# reclone-rise.net
KiCad netlist of a schematic drawn in EAGLE
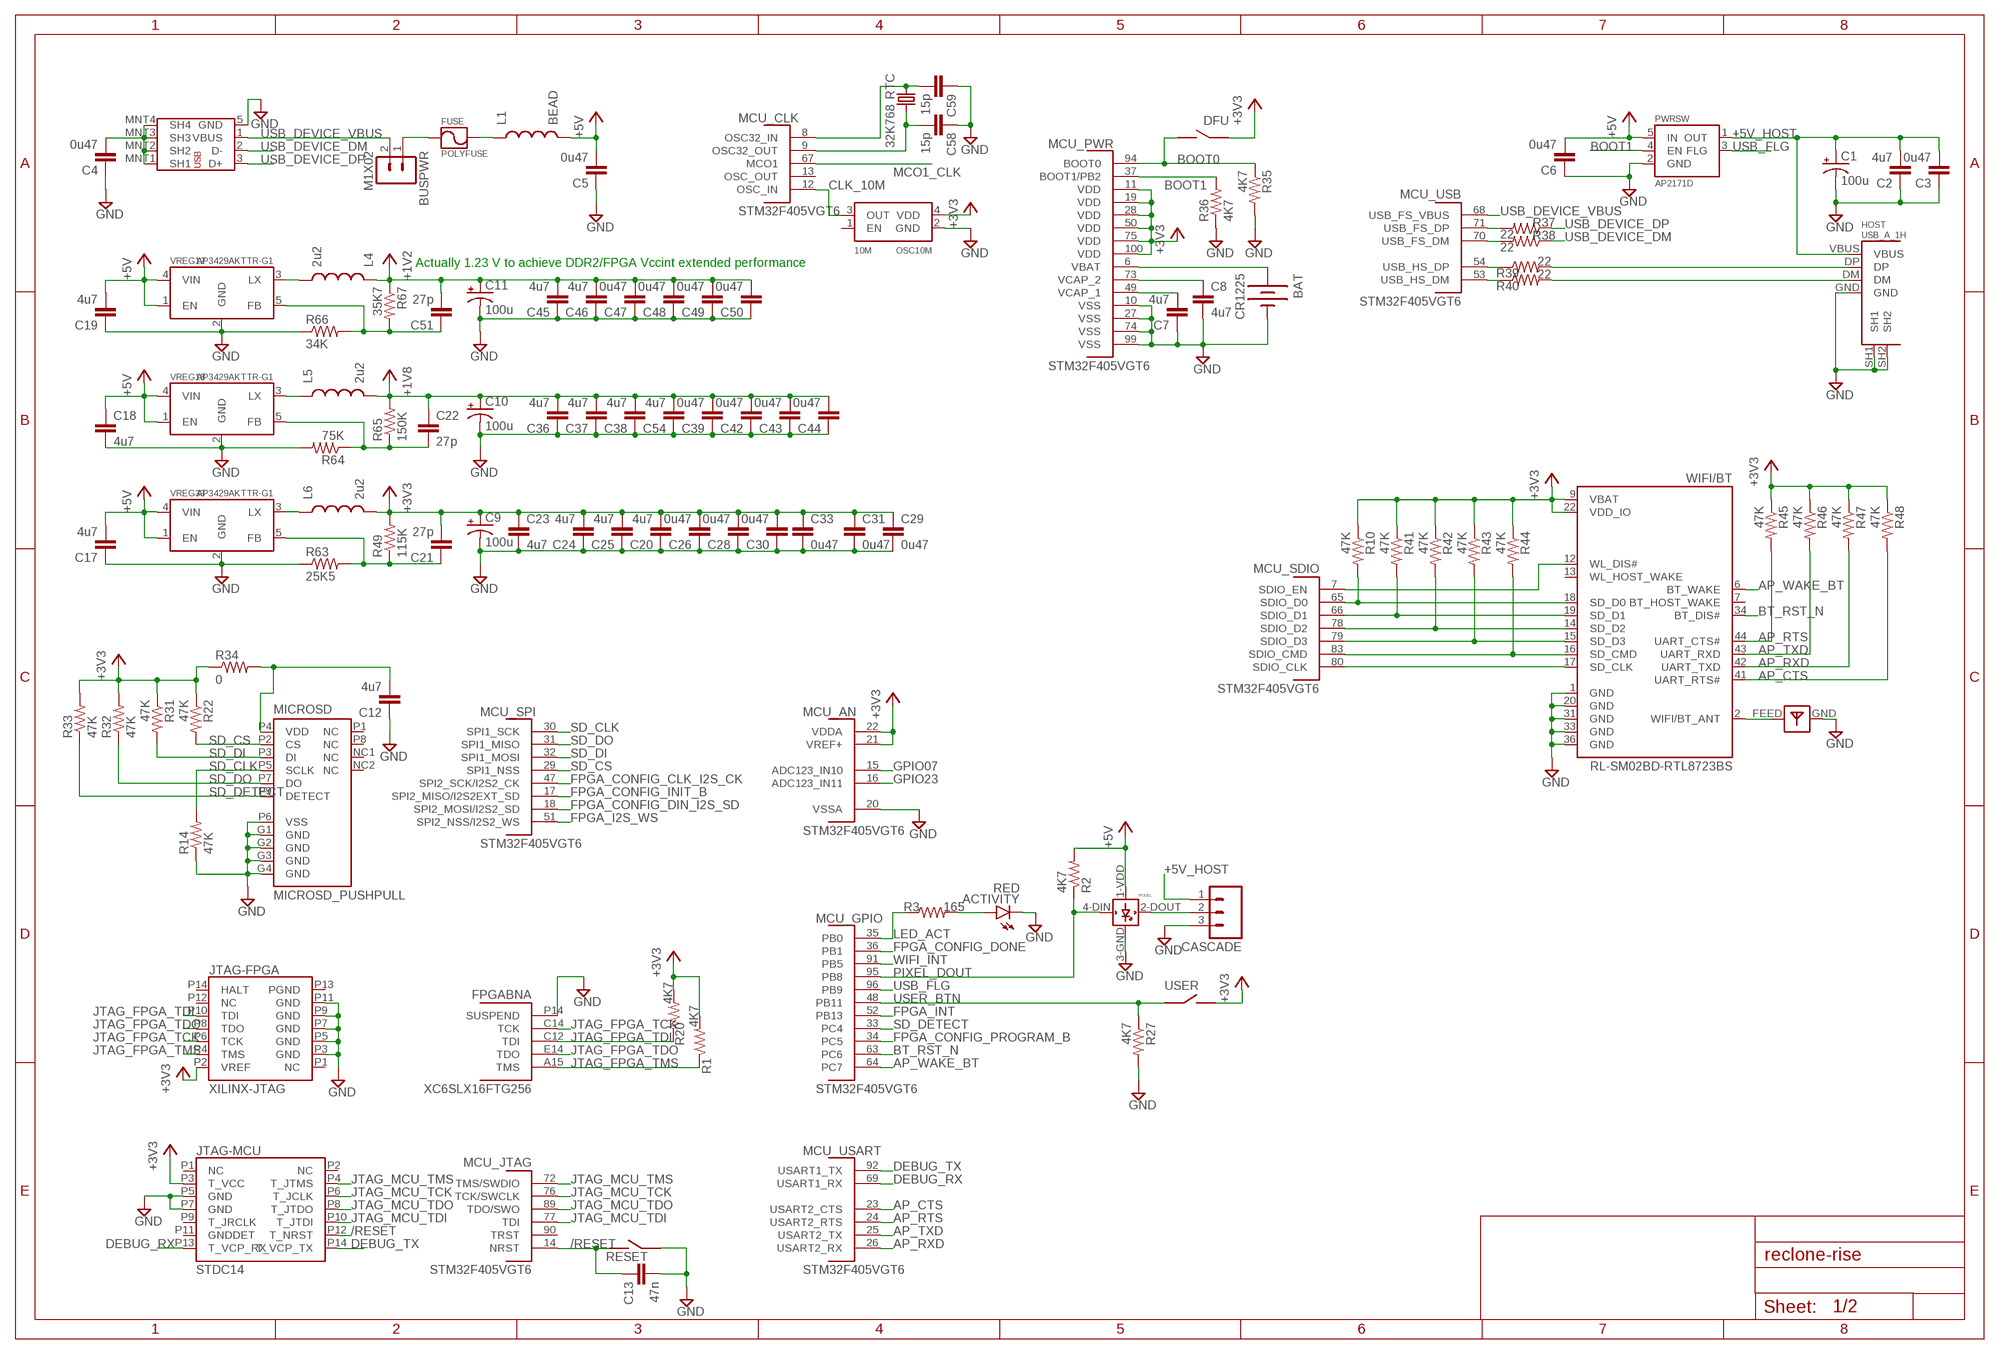
[diagram p0: schematic, sheet 1]
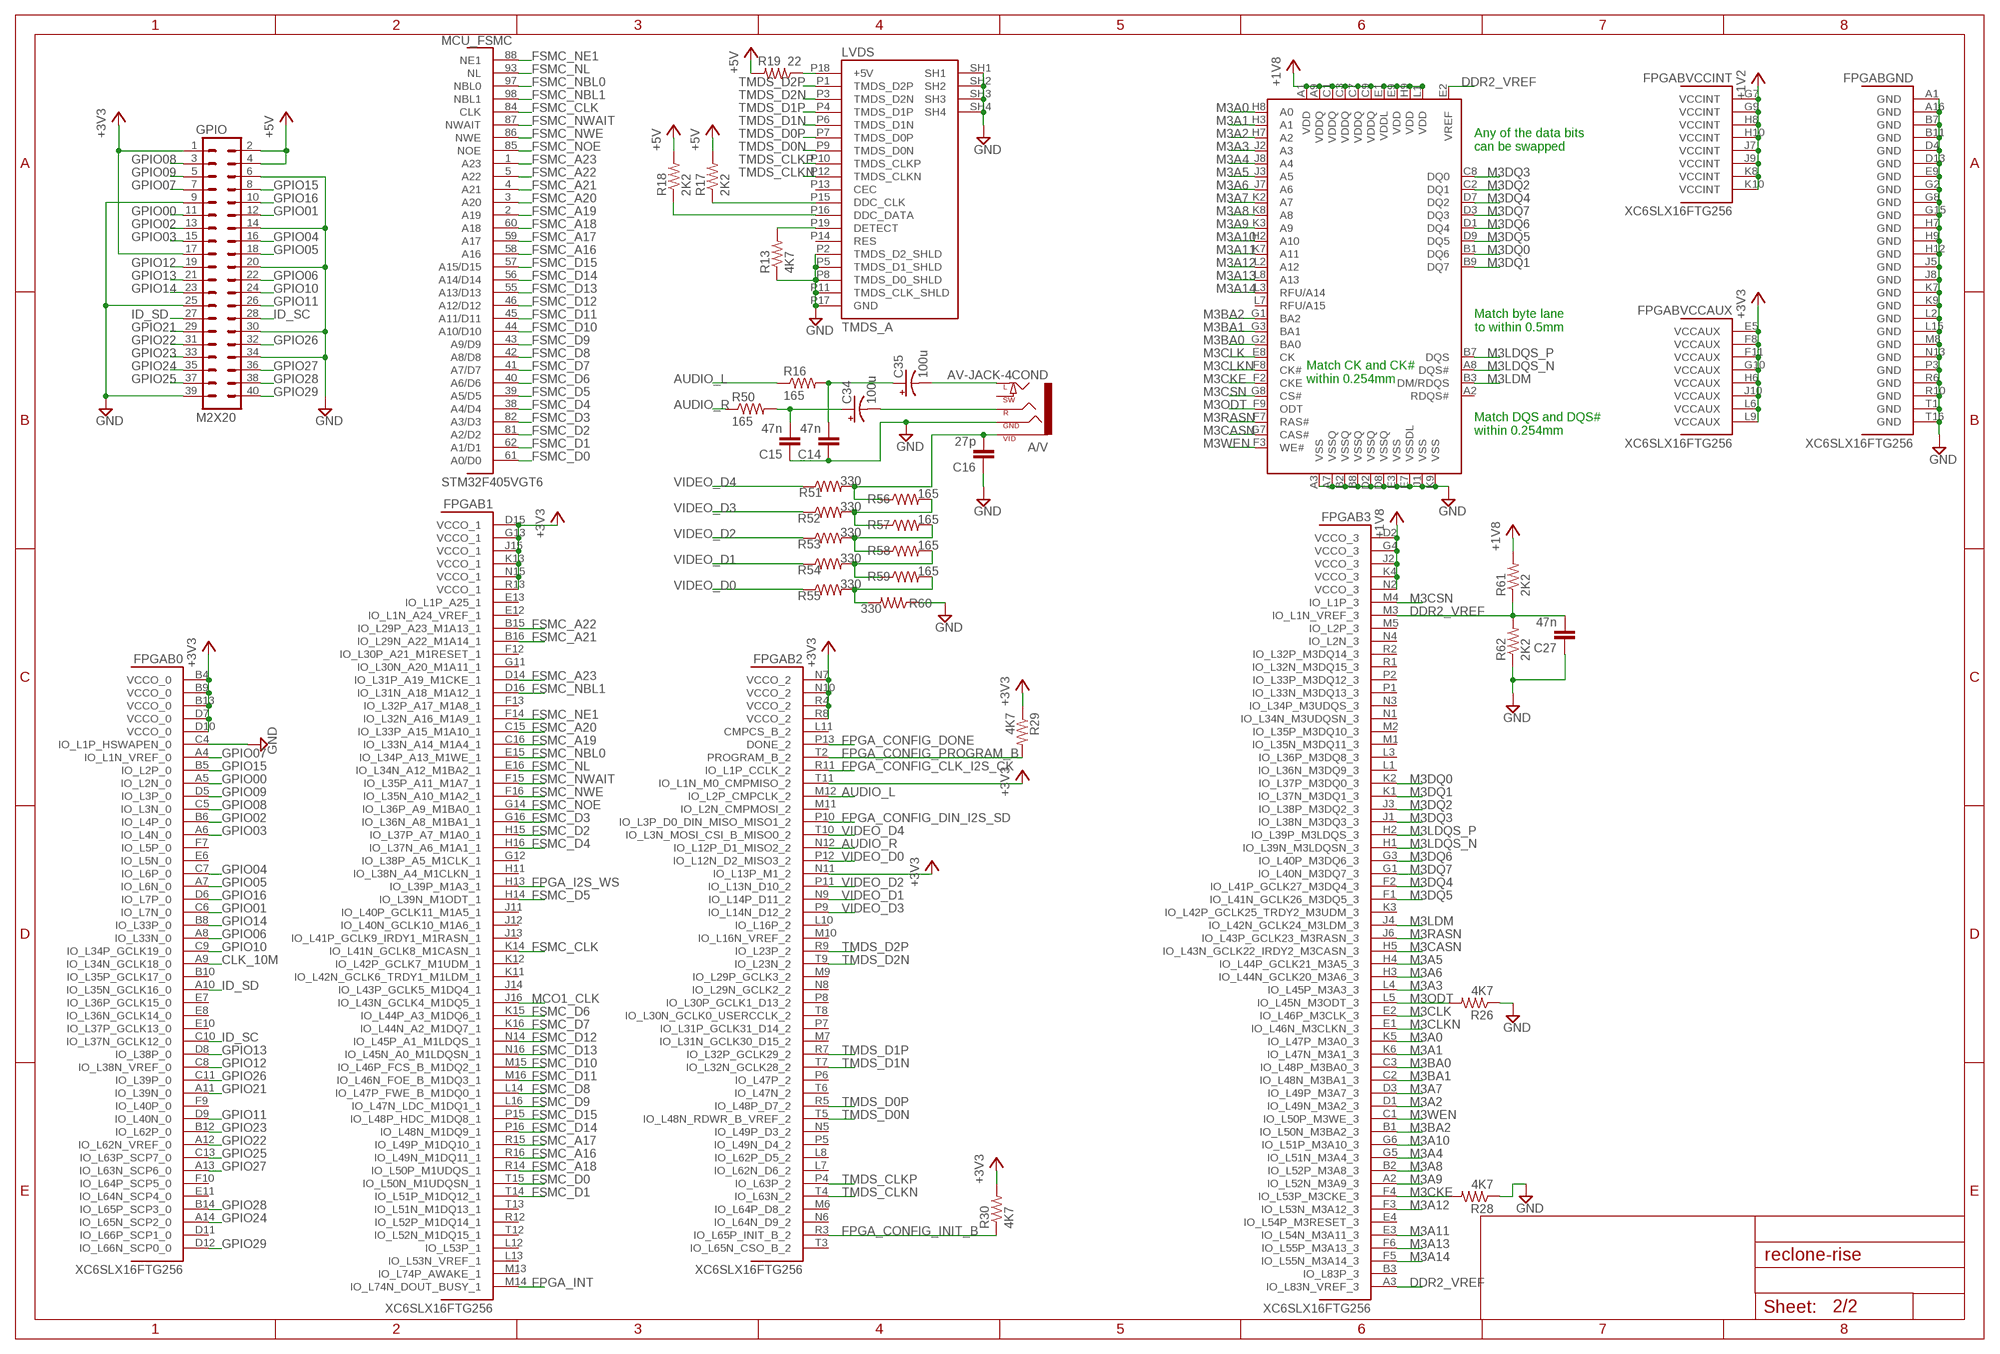
[diagram p1: schematic, sheet 2]

(export (version "E")
  (design (tool "Eeschema 10.0.6"))
  (components
    (comp (ref "A/V")
      (value "AV-JACK-4COND")
      (footprint "eagle-import:AV-JACK-3.5MM-4COND-SMD")
      (fields (field (name "MANF") "CUI Devices"))
      (libsource (lib "eagle-import") (part "AV-JACK-4COND"))
    )
    (comp (ref "C14")
      (value "47n")
      (footprint "eagle-import:0603-CAP")
      (fields (field (name "MANF") "Samsung Electro-Mechanics"))
      (libsource (lib "eagle-import") (part "CAP0603-CAP"))
    )
    (comp (ref "C15")
      (value "47n")
      (footprint "eagle-import:0603-CAP")
      (fields (field (name "MANF") "Samsung Electro-Mechanics"))
      (libsource (lib "eagle-import") (part "CAP0603-CAP"))
    )
    (comp (ref "C16")
      (value "27p")
      (footprint "eagle-import:0603-CAP")
      (fields (field (name "MANF") "KEMET"))
      (libsource (lib "eagle-import") (part "CAP0603-CAP"))
    )
    (comp (ref "C27")
      (value "47n")
      (footprint "eagle-import:0603-CAP")
      (fields (field (name "MANF") "Samsung Electro-Mechanics"))
      (libsource (lib "eagle-import") (part "CAP0603-CAP"))
    )
    (comp (ref "C34")
      (value "100u")
      (footprint "eagle-import:EIA3216")
      (fields (field (name "MANF") "Samsung Electro-Mechanics"))
      (libsource (lib "eagle-import") (part "CAP_POL1206"))
    )
    (comp (ref "C35")
      (value "100u")
      (footprint "eagle-import:EIA3216")
      (fields (field (name "MANF") "Samsung Electro-Mechanics"))
      (libsource (lib "eagle-import") (part "CAP_POL1206"))
    )
    (comp (ref "FPGA")
      (value "XC6SLX16FTG256")
      (footprint "eagle-import:FT256")
      (fields
        (field (name "DIGIKEY#") "122-1672-ND")
        (field (name "MANF") "Xilinx Inc.")
        (field (name "MANF#") "XC6SLX16-2FTG256C")
      )
      (libsource (lib "eagle-import") (part "XC6SLX16FTG256"))
    )
    (comp (ref "GPIO")
      (value "M2X20")
      (footprint "eagle-import:2X20")
      (fields (field (name "MANF") "Sullins Connector Solutions"))
      (libsource (lib "eagle-import") (part "M2X20"))
    )
    (comp (ref "LVDS")
      (value "TMDS_A")
      (footprint "eagle-import:TMDS_A_SMT")
      (fields (field (name "MANF") "FCI"))
      (libsource (lib "eagle-import") (part "TMDS_A"))
    )
    (comp (ref "MCU")
      (value "STM32F405VGT6")
      (footprint "eagle-import:LQFP-100")
      (fields (field (name "MANF") "STMicroelectronics"))
      (libsource (lib "eagle-import") (part "STM32F405VGT6"))
    )
    (comp (ref "R13")
      (value "4K7")
      (footprint "eagle-import:0603-RES")
      (fields (field (name "MANF") "Yageo"))
      (libsource (lib "eagle-import") (part "RESISTOR0603-RES"))
    )
    (comp (ref "R16")
      (value "165")
      (footprint "eagle-import:0603-RES")
      (fields (field (name "MANF") "Yageo"))
      (libsource (lib "eagle-import") (part "RESISTOR0603-RES"))
    )
    (comp (ref "R17")
      (value "2K2")
      (footprint "eagle-import:0603-RES")
      (fields (field (name "MANF") "Yageo"))
      (libsource (lib "eagle-import") (part "RESISTOR0603-RES"))
    )
    (comp (ref "R18")
      (value "2K2")
      (footprint "eagle-import:0603-RES")
      (fields (field (name "MANF") "Yageo"))
      (libsource (lib "eagle-import") (part "RESISTOR0603-RES"))
    )
    (comp (ref "R19")
      (value "22")
      (footprint "eagle-import:0603-RES")
      (fields (field (name "MANF") "Yageo"))
      (libsource (lib "eagle-import") (part "RESISTOR0603-RES"))
    )
    (comp (ref "R26")
      (value "4K7")
      (footprint "eagle-import:0603-RES")
      (fields (field (name "MANF") "Yageo"))
      (libsource (lib "eagle-import") (part "RESISTOR0603-RES"))
    )
    (comp (ref "R28")
      (value "4K7")
      (footprint "eagle-import:0603-RES")
      (fields (field (name "MANF") "Yageo"))
      (libsource (lib "eagle-import") (part "RESISTOR0603-RES"))
    )
    (comp (ref "R29")
      (value "4K7")
      (footprint "eagle-import:0603-RES")
      (fields (field (name "MANF") "Yageo"))
      (libsource (lib "eagle-import") (part "RESISTOR0603-RES"))
    )
    (comp (ref "R30")
      (value "4K7")
      (footprint "eagle-import:0603-RES")
      (fields (field (name "MANF") "Yageo"))
      (libsource (lib "eagle-import") (part "RESISTOR0603-RES"))
    )
    (comp (ref "R50")
      (value "165")
      (footprint "eagle-import:0603-RES")
      (fields (field (name "MANF") "Yageo"))
      (libsource (lib "eagle-import") (part "RESISTOR0603-RES"))
    )
    (comp (ref "R51")
      (value "330")
      (footprint "eagle-import:0603-RES")
      (fields (field (name "MANF") "Yageo"))
      (libsource (lib "eagle-import") (part "RESISTOR0603-RES"))
    )
    (comp (ref "R52")
      (value "330")
      (footprint "eagle-import:0603-RES")
      (fields (field (name "MANF") "Yageo"))
      (libsource (lib "eagle-import") (part "RESISTOR0603-RES"))
    )
    (comp (ref "R53")
      (value "330")
      (footprint "eagle-import:0603-RES")
      (fields (field (name "MANF") "Yageo"))
      (libsource (lib "eagle-import") (part "RESISTOR0603-RES"))
    )
    (comp (ref "R54")
      (value "330")
      (footprint "eagle-import:0603-RES")
      (fields (field (name "MANF") "Yageo"))
      (libsource (lib "eagle-import") (part "RESISTOR0603-RES"))
    )
    (comp (ref "R55")
      (value "330")
      (footprint "eagle-import:0603-RES")
      (fields (field (name "MANF") "Yageo"))
      (libsource (lib "eagle-import") (part "RESISTOR0603-RES"))
    )
    (comp (ref "R56")
      (value "165")
      (footprint "eagle-import:0603-RES")
      (fields (field (name "MANF") "Yageo"))
      (libsource (lib "eagle-import") (part "RESISTOR0603-RES"))
    )
    (comp (ref "R57")
      (value "165")
      (footprint "eagle-import:0603-RES")
      (fields (field (name "MANF") "Yageo"))
      (libsource (lib "eagle-import") (part "RESISTOR0603-RES"))
    )
    (comp (ref "R58")
      (value "165")
      (footprint "eagle-import:0603-RES")
      (fields (field (name "MANF") "Yageo"))
      (libsource (lib "eagle-import") (part "RESISTOR0603-RES"))
    )
    (comp (ref "R59")
      (value "165")
      (footprint "eagle-import:0603-RES")
      (fields (field (name "MANF") "Yageo"))
      (libsource (lib "eagle-import") (part "RESISTOR0603-RES"))
    )
    (comp (ref "R60")
      (value "330")
      (footprint "eagle-import:0603-RES")
      (fields (field (name "MANF") "Yageo"))
      (libsource (lib "eagle-import") (part "RESISTOR0603-RES"))
    )
    (comp (ref "R61")
      (value "2K2")
      (footprint "eagle-import:0603-RES")
      (fields (field (name "MANF") "Yageo"))
      (libsource (lib "eagle-import") (part "RESISTOR0603-RES"))
    )
    (comp (ref "R62")
      (value "2K2")
      (footprint "eagle-import:0603-RES")
      (fields (field (name "MANF") "Yageo"))
      (libsource (lib "eagle-import") (part "RESISTOR0603-RES"))
    )
    (comp (ref "RAM")
      (value "DDR2_X8")
      (footprint "eagle-import:60-FBGA-9X11.5")
      (fields (field (name "MANF") "ISSI Integrated Silicon Solution Inc"))
      (libsource (lib "eagle-import") (part "DDR2_X8"))
    )
    (comp (ref "ACTIVITY")
      (value "RED")
      (footprint "eagle-import:LED-0603")
      (fields (field (name "MANF") "Wurth Electronics Inc."))
      (libsource (lib "eagle-import") (part "LED0603"))
    )
    (comp (ref "ANTENNA")
      (value "ANTENNA_MEANDER_2.4GHZ")
      (footprint "eagle-import:MEANDER_ANTENNA_2.4GHZ")
      (libsource (lib "eagle-import") (part "ANTENNA_MEANDER_2.4GHZ"))
    )
    (comp (ref "BAT")
      (value "CR1225")
      (footprint "eagle-import:BATTCON_12MM")
      (fields (field (name "MANF") "Keystone Electronics"))
      (libsource (lib "eagle-import") (part "BATTERY12MM"))
    )
    (comp (ref "BUSPWR")
      (value "M1X02")
      (footprint "eagle-import:1X2-RTANG")
      (fields (field (name "MANF") "Sullins Connector Solutions"))
      (libsource (lib "eagle-import") (part "M1X02"))
    )
    (comp (ref "C1")
      (value "100u")
      (footprint "eagle-import:EIA3216")
      (fields (field (name "MANF") "Samsung Electro-Mechanics"))
      (libsource (lib "eagle-import") (part "CAP_POL1206"))
    )
    (comp (ref "C2")
      (value "4u7")
      (footprint "eagle-import:0603-CAP")
      (fields (field (name "MANF") "Samsung Electro-Mechanics"))
      (libsource (lib "eagle-import") (part "CAP0603-CAP"))
    )
    (comp (ref "C3")
      (value "0u47")
      (footprint "eagle-import:0603-CAP")
      (fields (field (name "MANF") "Samsung Electro-Mechanics"))
      (libsource (lib "eagle-import") (part "CAP0603-CAP"))
    )
    (comp (ref "C4")
      (value "0u47")
      (footprint "eagle-import:0603-CAP")
      (fields (field (name "MANF") "Samsung Electro-Mechanics"))
      (libsource (lib "eagle-import") (part "CAP0603-CAP"))
    )
    (comp (ref "C5")
      (value "0u47")
      (footprint "eagle-import:0603-CAP")
      (fields (field (name "MANF") "Samsung Electro-Mechanics"))
      (libsource (lib "eagle-import") (part "CAP0603-CAP"))
    )
    (comp (ref "C6")
      (value "0u47")
      (footprint "eagle-import:0603-CAP")
      (fields (field (name "MANF") "Samsung Electro-Mechanics"))
      (libsource (lib "eagle-import") (part "CAP0603-CAP"))
    )
    (comp (ref "C7")
      (value "4u7")
      (footprint "eagle-import:0603-CAP")
      (fields (field (name "MANF") "Samsung Electro-Mechanics"))
      (libsource (lib "eagle-import") (part "CAP0603-CAP"))
    )
    (comp (ref "C8")
      (value "4u7")
      (footprint "eagle-import:0603-CAP")
      (fields (field (name "MANF") "Samsung Electro-Mechanics"))
      (libsource (lib "eagle-import") (part "CAP0603-CAP"))
    )
    (comp (ref "C9")
      (value "100u")
      (footprint "eagle-import:EIA3216")
      (fields (field (name "MANF") "Samsung Electro-Mechanics"))
      (libsource (lib "eagle-import") (part "CAP_POL1206"))
    )
    (comp (ref "C10")
      (value "100u")
      (footprint "eagle-import:EIA3216")
      (fields (field (name "MANF") "Samsung Electro-Mechanics"))
      (libsource (lib "eagle-import") (part "CAP_POL1206"))
    )
    (comp (ref "C11")
      (value "100u")
      (footprint "eagle-import:EIA3216")
      (fields (field (name "MANF") "Samsung Electro-Mechanics"))
      (libsource (lib "eagle-import") (part "CAP_POL1206"))
    )
    (comp (ref "C12")
      (value "4u7")
      (footprint "eagle-import:0603-CAP")
      (fields (field (name "MANF") "Samsung Electro-Mechanics"))
      (libsource (lib "eagle-import") (part "CAP0603-CAP"))
    )
    (comp (ref "C13")
      (value "47n")
      (footprint "eagle-import:0603-CAP")
      (fields (field (name "MANF") "Samsung Electro-Mechanics"))
      (libsource (lib "eagle-import") (part "CAP0603-CAP"))
    )
    (comp (ref "C17")
      (value "4u7")
      (footprint "eagle-import:0603-CAP")
      (fields (field (name "MANF") "Samsung Electro-Mechanics"))
      (libsource (lib "eagle-import") (part "CAP0603-CAP"))
    )
    (comp (ref "C18")
      (value "4u7")
      (footprint "eagle-import:0603-CAP")
      (fields (field (name "MANF") "Samsung Electro-Mechanics"))
      (libsource (lib "eagle-import") (part "CAP0603-CAP"))
    )
    (comp (ref "C19")
      (value "4u7")
      (footprint "eagle-import:0603-CAP")
      (fields (field (name "MANF") "Samsung Electro-Mechanics"))
      (libsource (lib "eagle-import") (part "CAP0603-CAP"))
    )
    (comp (ref "C20")
      (value "4u7")
      (footprint "eagle-import:0603-CAP")
      (fields (field (name "MANF") "Samsung Electro-Mechanics"))
      (libsource (lib "eagle-import") (part "CAP0603-CAP"))
    )
    (comp (ref "C21")
      (value "27p")
      (footprint "eagle-import:0603-CAP")
      (fields (field (name "MANF") "KEMET"))
      (libsource (lib "eagle-import") (part "CAP0603-CAP"))
    )
    (comp (ref "C22")
      (value "27p")
      (footprint "eagle-import:0603-CAP")
      (fields (field (name "MANF") "KEMET"))
      (libsource (lib "eagle-import") (part "CAP0603-CAP"))
    )
    (comp (ref "C23")
      (value "4u7")
      (footprint "eagle-import:0603-CAP")
      (fields (field (name "MANF") "Samsung Electro-Mechanics"))
      (libsource (lib "eagle-import") (part "CAP0603-CAP"))
    )
    (comp (ref "C24")
      (value "4u7")
      (footprint "eagle-import:0603-CAP")
      (fields (field (name "MANF") "Samsung Electro-Mechanics"))
      (libsource (lib "eagle-import") (part "CAP0603-CAP"))
    )
    (comp (ref "C25")
      (value "4u7")
      (footprint "eagle-import:0603-CAP")
      (fields (field (name "MANF") "Samsung Electro-Mechanics"))
      (libsource (lib "eagle-import") (part "CAP0603-CAP"))
    )
    (comp (ref "C26")
      (value "0u47")
      (footprint "eagle-import:0603-CAP")
      (fields (field (name "MANF") "Samsung Electro-Mechanics"))
      (libsource (lib "eagle-import") (part "CAP0603-CAP"))
    )
    (comp (ref "C28")
      (value "0u47")
      (footprint "eagle-import:0603-CAP")
      (fields (field (name "MANF") "Samsung Electro-Mechanics"))
      (libsource (lib "eagle-import") (part "CAP0603-CAP"))
    )
    (comp (ref "C29")
      (value "0u47")
      (footprint "eagle-import:0603-CAP")
      (fields (field (name "MANF") "Samsung Electro-Mechanics"))
      (libsource (lib "eagle-import") (part "CAP0603-CAP"))
    )
    (comp (ref "C30")
      (value "0u47")
      (footprint "eagle-import:0603-CAP")
      (fields (field (name "MANF") "Samsung Electro-Mechanics"))
      (libsource (lib "eagle-import") (part "CAP0603-CAP"))
    )
    (comp (ref "C31")
      (value "0u47")
      (footprint "eagle-import:0603-CAP")
      (fields (field (name "MANF") "Samsung Electro-Mechanics"))
      (libsource (lib "eagle-import") (part "CAP0603-CAP"))
    )
    (comp (ref "C33")
      (value "0u47")
      (footprint "eagle-import:0603-CAP")
      (fields (field (name "MANF") "Samsung Electro-Mechanics"))
      (libsource (lib "eagle-import") (part "CAP0603-CAP"))
    )
    (comp (ref "C36")
      (value "4u7")
      (footprint "eagle-import:0603-CAP")
      (fields (field (name "MANF") "Samsung Electro-Mechanics"))
      (libsource (lib "eagle-import") (part "CAP0603-CAP"))
    )
    (comp (ref "C37")
      (value "4u7")
      (footprint "eagle-import:0603-CAP")
      (fields (field (name "MANF") "Samsung Electro-Mechanics"))
      (libsource (lib "eagle-import") (part "CAP0603-CAP"))
    )
    (comp (ref "C38")
      (value "4u7")
      (footprint "eagle-import:0603-CAP")
      (fields (field (name "MANF") "Samsung Electro-Mechanics"))
      (libsource (lib "eagle-import") (part "CAP0603-CAP"))
    )
    (comp (ref "C39")
      (value "0u47")
      (footprint "eagle-import:0603-CAP")
      (fields (field (name "MANF") "Samsung Electro-Mechanics"))
      (libsource (lib "eagle-import") (part "CAP0603-CAP"))
    )
    (comp (ref "C42")
      (value "0u47")
      (footprint "eagle-import:0603-CAP")
      (fields (field (name "MANF") "Samsung Electro-Mechanics"))
      (libsource (lib "eagle-import") (part "CAP0603-CAP"))
    )
    (comp (ref "C43")
      (value "0u47")
      (footprint "eagle-import:0603-CAP")
      (fields (field (name "MANF") "Samsung Electro-Mechanics"))
      (libsource (lib "eagle-import") (part "CAP0603-CAP"))
    )
    (comp (ref "C44")
      (value "0u47")
      (footprint "eagle-import:0603-CAP")
      (fields (field (name "MANF") "Samsung Electro-Mechanics"))
      (libsource (lib "eagle-import") (part "CAP0603-CAP"))
    )
    (comp (ref "C45")
      (value "4u7")
      (footprint "eagle-import:0603-CAP")
      (fields (field (name "MANF") "Samsung Electro-Mechanics"))
      (libsource (lib "eagle-import") (part "CAP0603-CAP"))
    )
    (comp (ref "C46")
      (value "4u7")
      (footprint "eagle-import:0603-CAP")
      (fields (field (name "MANF") "Samsung Electro-Mechanics"))
      (libsource (lib "eagle-import") (part "CAP0603-CAP"))
    )
    (comp (ref "C47")
      (value "0u47")
      (footprint "eagle-import:0603-CAP")
      (fields (field (name "MANF") "Samsung Electro-Mechanics"))
      (libsource (lib "eagle-import") (part "CAP0603-CAP"))
    )
    (comp (ref "C48")
      (value "0u47")
      (footprint "eagle-import:0603-CAP")
      (fields (field (name "MANF") "Samsung Electro-Mechanics"))
      (libsource (lib "eagle-import") (part "CAP0603-CAP"))
    )
    (comp (ref "C49")
      (value "0u47")
      (footprint "eagle-import:0603-CAP")
      (fields (field (name "MANF") "Samsung Electro-Mechanics"))
      (libsource (lib "eagle-import") (part "CAP0603-CAP"))
    )
    (comp (ref "C50")
      (value "0u47")
      (footprint "eagle-import:0603-CAP")
      (fields (field (name "MANF") "Samsung Electro-Mechanics"))
      (libsource (lib "eagle-import") (part "CAP0603-CAP"))
    )
    (comp (ref "C51")
      (value "27p")
      (footprint "eagle-import:0603-CAP")
      (fields (field (name "MANF") "KEMET"))
      (libsource (lib "eagle-import") (part "CAP0603-CAP"))
    )
    (comp (ref "C54")
      (value "4u7")
      (footprint "eagle-import:0603-CAP")
      (fields (field (name "MANF") "Samsung Electro-Mechanics"))
      (libsource (lib "eagle-import") (part "CAP0603-CAP"))
    )
    (comp (ref "C58")
      (value "15p")
      (footprint "eagle-import:0603-CAP")
      (fields (field (name "MANF") "AVX Corporation"))
      (libsource (lib "eagle-import") (part "CAP0603-CAP"))
    )
    (comp (ref "C59")
      (value "15p")
      (footprint "eagle-import:0603-CAP")
      (fields (field (name "MANF") "AVX Corporation"))
      (libsource (lib "eagle-import") (part "CAP0603-CAP"))
    )
    (comp (ref "CASCADE")
      (value "M03PTH")
      (footprint "eagle-import:1X03")
      (libsource (lib "eagle-import") (part "M03PTH"))
    )
    (comp (ref "DEVICE")
      (value "USB-MICRO-B-SMD")
      (footprint "eagle-import:USB-MICRO-B-SMD")
      (fields (field (name "MANF") "FCI"))
      (libsource (lib "eagle-import") (part "USB-MICRO-B-SMD"))
    )
    (comp (ref "DFU")
      (value "PTS636")
      (footprint "eagle-import:PB_TACT_PTH_6X3.5")
      (fields (field (name "MANF") "C&K"))
      (libsource (lib "eagle-import") (part "PTS636"))
    )
    (comp (ref "FUSE")
      (value "POLYFUSE")
      (footprint "eagle-import:1206L")
      (fields (field (name "MANF") "Bourns Inc."))
      (libsource (lib "eagle-import") (part "POLYFUSE"))
    )
    (comp (ref "HOST")
      (value "USB_A_1H")
      (footprint "eagle-import:USB-A-1H")
      (fields (field (name "MANF") "Amphenol ICC (FCI)"))
      (libsource (lib "eagle-import") (part "USB_A_1H"))
    )
    (comp (ref "JTAG-FPGA")
      (value "XILINX-JTAG")
      (footprint "eagle-import:XILINX-JTAG")
      (fields (field (name "MANF") "Molex"))
      (libsource (lib "eagle-import") (part "XILINX-JTAG"))
    )
    (comp (ref "JTAG-MCU")
      (value "STDC14")
      (footprint "eagle-import:PTH_14_1.27")
      (fields (field (name "MANF") "CNC Tech"))
      (libsource (lib "eagle-import") (part "STDC14"))
    )
    (comp (ref "L1")
      (value "BEAD")
      (footprint "eagle-import:0603")
      (fields (field (name "MANF") "Murata Electronics"))
      (libsource (lib "eagle-import") (part "INDUCTOR0603"))
    )
    (comp (ref "L4")
      (value "2u2")
      (footprint "eagle-import:0805")
      (fields (field (name "MANF") "Samsung Electro-Mechanics"))
      (libsource (lib "eagle-import") (part "INDUCTOR0805"))
    )
    (comp (ref "L5")
      (value "2u2")
      (footprint "eagle-import:0805")
      (fields (field (name "MANF") "Samsung Electro-Mechanics"))
      (libsource (lib "eagle-import") (part "INDUCTOR0805"))
    )
    (comp (ref "L6")
      (value "2u2")
      (footprint "eagle-import:0805")
      (fields (field (name "MANF") "Samsung Electro-Mechanics"))
      (libsource (lib "eagle-import") (part "INDUCTOR0805"))
    )
    (comp (ref "MICROSD")
      (value "MICROSD_PUSHPULL")
      (footprint "eagle-import:MICROSD_PUSHPULL")
      (fields (field (name "MANF") "Molex"))
      (libsource (lib "eagle-import") (part "MICROSD_PUSHPULL"))
    )
    (comp (ref "OSC10M")
      (value "10M")
      (footprint "eagle-import:OSC-5X3.2")
      (fields (field (name "MANF") "Fox Electronics"))
      (libsource (lib "eagle-import") (part "OSC_ENABLED_SMD"))
    )
    (comp (ref "PIXEL")
      (value "WS2812B")
      (footprint "eagle-import:WS2812B")
      (fields (field (name "MANF") "SparkFun Electronics"))
      (libsource (lib "eagle-import") (part "WS2812B"))
    )
    (comp (ref "PWRSW")
      (value "AP2171D")
      (footprint "eagle-import:SOT25")
      (fields (field (name "MANF") "Diodes Incorporated"))
      (libsource (lib "eagle-import") (part "AP2171D"))
    )
    (comp (ref "R1")
      (value "4K7")
      (footprint "eagle-import:0603-RES")
      (fields (field (name "MANF") "Yageo"))
      (libsource (lib "eagle-import") (part "RESISTOR0603-RES"))
    )
    (comp (ref "R2")
      (value "4K7")
      (footprint "eagle-import:0603-RES")
      (fields (field (name "MANF") "Yageo"))
      (libsource (lib "eagle-import") (part "RESISTOR0603-RES"))
    )
    (comp (ref "R3")
      (value "165")
      (footprint "eagle-import:0603-RES")
      (fields (field (name "MANF") "Yageo"))
      (libsource (lib "eagle-import") (part "RESISTOR0603-RES"))
    )
    (comp (ref "R10")
      (value "47K")
      (footprint "eagle-import:0603-RES")
      (fields (field (name "MANF") "Yageo"))
      (libsource (lib "eagle-import") (part "RESISTOR0603-RES"))
    )
    (comp (ref "R14")
      (value "47K")
      (footprint "eagle-import:0603-RES")
      (fields (field (name "MANF") "Yageo"))
      (libsource (lib "eagle-import") (part "RESISTOR0603-RES"))
    )
    (comp (ref "R20")
      (value "4K7")
      (footprint "eagle-import:0603-RES")
      (fields (field (name "MANF") "Yageo"))
      (libsource (lib "eagle-import") (part "RESISTOR0603-RES"))
    )
    (comp (ref "R22")
      (value "47K")
      (footprint "eagle-import:0603-RES")
      (fields (field (name "MANF") "Yageo"))
      (libsource (lib "eagle-import") (part "RESISTOR0603-RES"))
    )
    (comp (ref "R27")
      (value "4K7")
      (footprint "eagle-import:0603-RES")
      (fields (field (name "MANF") "Yageo"))
      (libsource (lib "eagle-import") (part "RESISTOR0603-RES"))
    )
    (comp (ref "R31")
      (value "47K")
      (footprint "eagle-import:0603-RES")
      (fields (field (name "MANF") "Yageo"))
      (libsource (lib "eagle-import") (part "RESISTOR0603-RES"))
    )
    (comp (ref "R32")
      (value "47K")
      (footprint "eagle-import:0603-RES")
      (fields (field (name "MANF") "Yageo"))
      (libsource (lib "eagle-import") (part "RESISTOR0603-RES"))
    )
    (comp (ref "R33")
      (value "47K")
      (footprint "eagle-import:0603-RES")
      (fields (field (name "MANF") "Yageo"))
      (libsource (lib "eagle-import") (part "RESISTOR0603-RES"))
    )
    (comp (ref "R34")
      (value "0")
      (footprint "eagle-import:0603-RES")
      (fields (field (name "MANF") "Yageo"))
      (libsource (lib "eagle-import") (part "RESISTOR0603-RES"))
    )
    (comp (ref "R35")
      (value "4K7")
      (footprint "eagle-import:0603-RES")
      (fields (field (name "MANF") "Yageo"))
      (libsource (lib "eagle-import") (part "RESISTOR0603-RES"))
    )
    (comp (ref "R36")
      (value "4K7")
      (footprint "eagle-import:0603-RES")
      (fields (field (name "MANF") "Yageo"))
      (libsource (lib "eagle-import") (part "RESISTOR0603-RES"))
    )
    (comp (ref "R37")
      (value "22")
      (footprint "eagle-import:0603-RES")
      (fields (field (name "MANF") "Yageo"))
      (libsource (lib "eagle-import") (part "RESISTOR0603-RES"))
    )
    (comp (ref "R38")
      (value "22")
      (footprint "eagle-import:0603-RES")
      (fields (field (name "MANF") "Yageo"))
      (libsource (lib "eagle-import") (part "RESISTOR0603-RES"))
    )
    (comp (ref "R39")
      (value "22")
      (footprint "eagle-import:0603-RES")
      (fields (field (name "MANF") "Yageo"))
      (libsource (lib "eagle-import") (part "RESISTOR0603-RES"))
    )
    (comp (ref "R40")
      (value "22")
      (footprint "eagle-import:0603-RES")
      (fields (field (name "MANF") "Yageo"))
      (libsource (lib "eagle-import") (part "RESISTOR0603-RES"))
    )
    (comp (ref "R41")
      (value "47K")
      (footprint "eagle-import:0603-RES")
      (fields (field (name "MANF") "Yageo"))
      (libsource (lib "eagle-import") (part "RESISTOR0603-RES"))
    )
    (comp (ref "R42")
      (value "47K")
      (footprint "eagle-import:0603-RES")
      (fields (field (name "MANF") "Yageo"))
      (libsource (lib "eagle-import") (part "RESISTOR0603-RES"))
    )
    (comp (ref "R43")
      (value "47K")
      (footprint "eagle-import:0603-RES")
      (fields (field (name "MANF") "Yageo"))
      (libsource (lib "eagle-import") (part "RESISTOR0603-RES"))
    )
    (comp (ref "R44")
      (value "47K")
      (footprint "eagle-import:0603-RES")
      (fields (field (name "MANF") "Yageo"))
      (libsource (lib "eagle-import") (part "RESISTOR0603-RES"))
    )
    (comp (ref "R45")
      (value "47K")
      (footprint "eagle-import:0603-RES")
      (fields (field (name "MANF") "Yageo"))
      (libsource (lib "eagle-import") (part "RESISTOR0603-RES"))
    )
    (comp (ref "R46")
      (value "47K")
      (footprint "eagle-import:0603-RES")
      (fields (field (name "MANF") "Yageo"))
      (libsource (lib "eagle-import") (part "RESISTOR0603-RES"))
    )
    (comp (ref "R47")
      (value "47K")
      (footprint "eagle-import:0603-RES")
      (fields (field (name "MANF") "Yageo"))
      (libsource (lib "eagle-import") (part "RESISTOR0603-RES"))
    )
    (comp (ref "R48")
      (value "47K")
      (footprint "eagle-import:0603-RES")
      (fields (field (name "MANF") "Yageo"))
      (libsource (lib "eagle-import") (part "RESISTOR0603-RES"))
    )
    (comp (ref "R49")
      (value "115K")
      (footprint "eagle-import:0603-RES")
      (fields (field (name "MANF") "Yageo"))
      (libsource (lib "eagle-import") (part "RESISTOR0603-RES"))
    )
    (comp (ref "R63")
      (value "25K5")
      (footprint "eagle-import:0603-RES")
      (fields (field (name "MANF") "Yageo"))
      (libsource (lib "eagle-import") (part "RESISTOR0603-RES"))
    )
    (comp (ref "R64")
      (value "75K")
      (footprint "eagle-import:0603-RES")
      (fields (field (name "MANF") "Yageo"))
      (libsource (lib "eagle-import") (part "RESISTOR0603-RES"))
    )
    (comp (ref "R65")
      (value "150K")
      (footprint "eagle-import:0603-RES")
      (fields (field (name "MANF") "Yageo"))
      (libsource (lib "eagle-import") (part "RESISTOR0603-RES"))
    )
    (comp (ref "R66")
      (value "34K")
      (footprint "eagle-import:0603-RES")
      (fields (field (name "MANF") "Yageo"))
      (libsource (lib "eagle-import") (part "RESISTOR0603-RES"))
    )
    (comp (ref "R67")
      (value "35K7")
      (footprint "eagle-import:0603-RES")
      (fields (field (name "MANF") "Yageo"))
      (libsource (lib "eagle-import") (part "RESISTOR0603-RES"))
    )
    (comp (ref "RESET")
      (value "PTS636")
      (footprint "eagle-import:PB_TACT_PTH_6X3.5")
      (fields (field (name "MANF") "C&K"))
      (libsource (lib "eagle-import") (part "PTS636"))
    )
    (comp (ref "RTC")
      (value "32K768")
      (footprint "eagle-import:CRYSTAL-32KHZ-SMD")
      (fields (field (name "MANF") "Cardinal Components Inc."))
      (libsource (lib "eagle-import") (part "CRYSTAL"))
    )
    (comp (ref "USER")
      (value "SPST_TACT_6X6")
      (footprint "eagle-import:PB_TACT_PTH_6X6")
      (fields (field (name "MANF") "TE Connectivity ALCOSWITCH Switches"))
      (libsource (lib "eagle-import") (part "SPST_TACT_6X6"))
    )
    (comp (ref "VREG12")
      (value "AP3429AKTTR-G1")
      (footprint "eagle-import:SOT-23-5")
      (fields (field (name "MANF") "Diodes Incorporated"))
      (libsource (lib "eagle-import") (part "AP3429A"))
    )
    (comp (ref "VREG18")
      (value "AP3429AKTTR-G1")
      (footprint "eagle-import:SOT-23-5")
      (fields (field (name "MANF") "Diodes Incorporated"))
      (libsource (lib "eagle-import") (part "AP3429A"))
    )
    (comp (ref "VREG33")
      (value "AP3429AKTTR-G1")
      (footprint "eagle-import:SOT-23-5")
      (fields (field (name "MANF") "Diodes Incorporated"))
      (libsource (lib "eagle-import") (part "AP3429A"))
    )
    (comp (ref "WIFI/BT")
      (value "RL-SM02BD-RTL8723BS")
      (footprint "eagle-import:LGA12-44")
      (fields (field (name "MANF") "Realtek"))
      (libsource (lib "eagle-import") (part "RL-SM02BD-RTL8723BS"))
    )
  )
  (nets
    (net (code "1") (name "+1V2") (class "Default")
      (node (ref "C11") (pin "A") (pinfunction "+_A") (pintype "passive"))
      (node (ref "C45") (pin "2") (pinfunction "2_2") (pintype "passive"))
      (node (ref "C46") (pin "2") (pinfunction "2_2") (pintype "passive"))
      (node (ref "C47") (pin "2") (pinfunction "2_2") (pintype "passive"))
      (node (ref "C48") (pin "2") (pinfunction "2_2") (pintype "passive"))
      (node (ref "C49") (pin "2") (pinfunction "2_2") (pintype "passive"))
      (node (ref "C50") (pin "2") (pinfunction "2_2") (pintype "passive"))
      (node (ref "C51") (pin "2") (pinfunction "2_2") (pintype "passive"))
      (node (ref "FPGA") (pin "G7") (pinfunction "VCCINT_G7") (pintype "input"))
      (node (ref "FPGA") (pin "G9") (pinfunction "VCCINT_G9") (pintype "input"))
      (node (ref "FPGA") (pin "H10") (pinfunction "VCCINT_H10") (pintype "input"))
      (node (ref "FPGA") (pin "H8") (pinfunction "VCCINT_H8") (pintype "input"))
      (node (ref "FPGA") (pin "J7") (pinfunction "VCCINT_J7") (pintype "input"))
      (node (ref "FPGA") (pin "J9") (pinfunction "VCCINT_J9") (pintype "input"))
      (node (ref "FPGA") (pin "K10") (pinfunction "VCCINT_K10") (pintype "input"))
      (node (ref "FPGA") (pin "K8") (pinfunction "VCCINT_K8") (pintype "input"))
      (node (ref "L4") (pin "1") (pinfunction "1_1") (pintype "passive"))
      (node (ref "R67") (pin "1") (pinfunction "1_1") (pintype "passive"))
    )
    (net (code "2") (name "+1V8") (class "Default")
      (node (ref "C10") (pin "A") (pinfunction "+_A") (pintype "passive"))
      (node (ref "C22") (pin "1") (pinfunction "1_1") (pintype "passive"))
      (node (ref "C36") (pin "2") (pinfunction "2_2") (pintype "passive"))
      (node (ref "C37") (pin "2") (pinfunction "2_2") (pintype "passive"))
      (node (ref "C38") (pin "2") (pinfunction "2_2") (pintype "passive"))
      (node (ref "C39") (pin "2") (pinfunction "2_2") (pintype "passive"))
      (node (ref "C42") (pin "2") (pinfunction "2_2") (pintype "passive"))
      (node (ref "C43") (pin "2") (pinfunction "2_2") (pintype "passive"))
      (node (ref "C44") (pin "2") (pinfunction "2_2") (pintype "passive"))
      (node (ref "C54") (pin "2") (pinfunction "2_2") (pintype "passive"))
      (node (ref "FPGA") (pin "D2") (pinfunction "VCCO_3_D2") (pintype "input"))
      (node (ref "FPGA") (pin "G4") (pinfunction "VCCO_3_G4") (pintype "input"))
      (node (ref "FPGA") (pin "J2") (pinfunction "VCCO_3_J2") (pintype "input"))
      (node (ref "FPGA") (pin "K4") (pinfunction "VCCO_3_K4") (pintype "input"))
      (node (ref "FPGA") (pin "N2") (pinfunction "VCCO_3_N2") (pintype "input"))
      (node (ref "L5") (pin "2") (pinfunction "2_2") (pintype "passive"))
      (node (ref "R61") (pin "2") (pinfunction "2_2") (pintype "passive"))
      (node (ref "R65") (pin "2") (pinfunction "2_2") (pintype "passive"))
      (node (ref "RAM") (pin "A1") (pinfunction "VDD_A1") (pintype "bidirectional"))
      (node (ref "RAM") (pin "A9") (pinfunction "VDDQ_A9") (pintype "bidirectional"))
      (node (ref "RAM") (pin "C1") (pinfunction "VDDQ_C1") (pintype "bidirectional"))
      (node (ref "RAM") (pin "C3") (pinfunction "VDDQ_C3") (pintype "bidirectional"))
      (node (ref "RAM") (pin "C7") (pinfunction "VDDQ_C7") (pintype "bidirectional"))
      (node (ref "RAM") (pin "C9") (pinfunction "VDDQ_C9") (pintype "bidirectional"))
      (node (ref "RAM") (pin "E1") (pinfunction "VDDL_E1") (pintype "bidirectional"))
      (node (ref "RAM") (pin "E9") (pinfunction "VDD_E9") (pintype "bidirectional"))
      (node (ref "RAM") (pin "H9") (pinfunction "VDD_H9") (pintype "bidirectional"))
      (node (ref "RAM") (pin "L1") (pinfunction "VDD_L1") (pintype "bidirectional"))
    )
    (net (code "3") (name "+3V3") (class "Default")
      (node (ref "C20") (pin "2") (pinfunction "2_2") (pintype "passive"))
      (node (ref "C21") (pin "2") (pinfunction "2_2") (pintype "passive"))
      (node (ref "C23") (pin "1") (pinfunction "1_1") (pintype "passive"))
      (node (ref "C24") (pin "2") (pinfunction "2_2") (pintype "passive"))
      (node (ref "C25") (pin "2") (pinfunction "2_2") (pintype "passive"))
      (node (ref "C26") (pin "2") (pinfunction "2_2") (pintype "passive"))
      (node (ref "C28") (pin "2") (pinfunction "2_2") (pintype "passive"))
      (node (ref "C29") (pin "1") (pinfunction "1_1") (pintype "passive"))
      (node (ref "C30") (pin "2") (pinfunction "2_2") (pintype "passive"))
      (node (ref "C31") (pin "1") (pinfunction "1_1") (pintype "passive"))
      (node (ref "C33") (pin "1") (pinfunction "1_1") (pintype "passive"))
      (node (ref "C9") (pin "A") (pinfunction "+_A") (pintype "passive"))
      (node (ref "DFU") (pin "1") (pinfunction "A_1") (pintype "bidirectional"))
      (node (ref "FPGA") (pin "B13") (pinfunction "VCCO_0_B13") (pintype "input"))
      (node (ref "FPGA") (pin "B4") (pinfunction "VCCO_0_B4") (pintype "input"))
      (node (ref "FPGA") (pin "B9") (pinfunction "VCCO_0_B9") (pintype "input"))
      (node (ref "FPGA") (pin "D10") (pinfunction "VCCO_0_D10") (pintype "input"))
      (node (ref "FPGA") (pin "D15") (pinfunction "VCCO_1_D15") (pintype "input"))
      (node (ref "FPGA") (pin "D7") (pinfunction "VCCO_0_D7") (pintype "input"))
      (node (ref "FPGA") (pin "E5") (pinfunction "VCCAUX_E5") (pintype "input"))
      (node (ref "FPGA") (pin "F11") (pinfunction "VCCAUX_F11") (pintype "input"))
      (node (ref "FPGA") (pin "F8") (pinfunction "VCCAUX_F8") (pintype "input"))
      (node (ref "FPGA") (pin "G10") (pinfunction "VCCAUX_G10") (pintype "input"))
      (node (ref "FPGA") (pin "G13") (pinfunction "VCCO_1_G13") (pintype "input"))
      (node (ref "FPGA") (pin "H6") (pinfunction "VCCAUX_H6") (pintype "input"))
      (node (ref "FPGA") (pin "J10") (pinfunction "VCCAUX_J10") (pintype "input"))
      (node (ref "FPGA") (pin "J15") (pinfunction "VCCO_1_J15") (pintype "input"))
      (node (ref "FPGA") (pin "K13") (pinfunction "VCCO_1_K13") (pintype "input"))
      (node (ref "FPGA") (pin "L6") (pinfunction "VCCAUX_L6") (pintype "input"))
      (node (ref "FPGA") (pin "L9") (pinfunction "VCCAUX_L9") (pintype "input"))
      (node (ref "FPGA") (pin "N10") (pinfunction "VCCO_2_N10") (pintype "input"))
      (node (ref "FPGA") (pin "N11") (pinfunction "IO_L13P_M1_2_N11") (pintype "bidirectional"))
      (node (ref "FPGA") (pin "N15") (pinfunction "VCCO_1_N15") (pintype "input"))
      (node (ref "FPGA") (pin "N7") (pinfunction "VCCO_2_N7") (pintype "input"))
      (node (ref "FPGA") (pin "R13") (pinfunction "VCCO_1_R13") (pintype "input"))
      (node (ref "FPGA") (pin "R4") (pinfunction "VCCO_2_R4") (pintype "input"))
      (node (ref "FPGA") (pin "R8") (pinfunction "VCCO_2_R8") (pintype "input"))
      (node (ref "FPGA") (pin "T11") (pinfunction "IO_L1N_M0_CMPMISO_2_T11") (pintype "bidirectional"))
      (node (ref "GPIO") (pin "1") (pinfunction "1_1") (pintype "passive"))
      (node (ref "GPIO") (pin "17") (pinfunction "17_17") (pintype "passive"))
      (node (ref "JTAG-FPGA") (pin "P2") (pinfunction "VREF_P2") (pintype "bidirectional"))
      (node (ref "JTAG-MCU") (pin "P3") (pinfunction "T_VCC_P3") (pintype "bidirectional"))
      (node (ref "L6") (pin "2") (pinfunction "2_2") (pintype "passive"))
      (node (ref "MCU") (pin "100") (pinfunction "VDD_100") (pintype "bidirectional"))
      (node (ref "MCU") (pin "11") (pinfunction "VDD_11") (pintype "bidirectional"))
      (node (ref "MCU") (pin "19") (pinfunction "VDD_19") (pintype "bidirectional"))
      (node (ref "MCU") (pin "21") (pinfunction "VREF+_21") (pintype "bidirectional"))
      (node (ref "MCU") (pin "22") (pinfunction "VDDA_22") (pintype "bidirectional"))
      (node (ref "MCU") (pin "28") (pinfunction "VDD_28") (pintype "bidirectional"))
      (node (ref "MCU") (pin "50") (pinfunction "VDD_50") (pintype "bidirectional"))
      (node (ref "MCU") (pin "75") (pinfunction "VDD_75") (pintype "bidirectional"))
      (node (ref "OSC10M") (pin "4") (pinfunction "VDD_4") (pintype "bidirectional"))
      (node (ref "R1") (pin "2") (pinfunction "2_2") (pintype "passive"))
      (node (ref "R10") (pin "1") (pinfunction "1_1") (pintype "passive"))
      (node (ref "R20") (pin "2") (pinfunction "2_2") (pintype "passive"))
      (node (ref "R22") (pin "1") (pinfunction "1_1") (pintype "passive"))
      (node (ref "R29") (pin "1") (pinfunction "1_1") (pintype "passive"))
      (node (ref "R30") (pin "2") (pinfunction "2_2") (pintype "passive"))
      (node (ref "R31") (pin "1") (pinfunction "1_1") (pintype "passive"))
      (node (ref "R32") (pin "2") (pinfunction "2_2") (pintype "passive"))
      (node (ref "R33") (pin "2") (pinfunction "2_2") (pintype "passive"))
      (node (ref "R34") (pin "1") (pinfunction "1_1") (pintype "passive"))
      (node (ref "R41") (pin "1") (pinfunction "1_1") (pintype "passive"))
      (node (ref "R42") (pin "1") (pinfunction "1_1") (pintype "passive"))
      (node (ref "R43") (pin "1") (pinfunction "1_1") (pintype "passive"))
      (node (ref "R44") (pin "1") (pinfunction "1_1") (pintype "passive"))
      (node (ref "R45") (pin "1") (pinfunction "1_1") (pintype "passive"))
      (node (ref "R46") (pin "1") (pinfunction "1_1") (pintype "passive"))
      (node (ref "R47") (pin "1") (pinfunction "1_1") (pintype "passive"))
      (node (ref "R48") (pin "1") (pinfunction "1_1") (pintype "passive"))
      (node (ref "R49") (pin "2") (pinfunction "2_2") (pintype "passive"))
      (node (ref "USER") (pin "3") (pinfunction "B_3") (pintype "bidirectional"))
      (node (ref "WIFI/BT") (pin "22") (pinfunction "VDD_IO_22") (pintype "bidirectional"))
      (node (ref "WIFI/BT") (pin "9") (pinfunction "VBAT_9") (pintype "bidirectional"))
    )
    (net (code "4") (name "+5V") (class "Default")
      (node (ref "C17") (pin "2") (pinfunction "2_2") (pintype "passive"))
      (node (ref "C18") (pin "1") (pinfunction "1_1") (pintype "passive"))
      (node (ref "C19") (pin "2") (pinfunction "2_2") (pintype "passive"))
      (node (ref "C5") (pin "2") (pinfunction "2_2") (pintype "passive"))
      (node (ref "C6") (pin "2") (pinfunction "2_2") (pintype "passive"))
      (node (ref "GPIO") (pin "2") (pinfunction "2_2") (pintype "passive"))
      (node (ref "GPIO") (pin "4") (pinfunction "4_4") (pintype "passive"))
      (node (ref "L1") (pin "2") (pinfunction "2_2") (pintype "passive"))
      (node (ref "PIXEL") (pin "1-VDD") (pinfunction "VDD_1-VDD") (pintype "bidirectional"))
      (node (ref "PWRSW") (pin "5") (pinfunction "IN_5") (pintype "bidirectional"))
      (node (ref "R17") (pin "2") (pinfunction "2_2") (pintype "passive"))
      (node (ref "R18") (pin "2") (pinfunction "2_2") (pintype "passive"))
      (node (ref "R19") (pin "2") (pinfunction "2_2") (pintype "passive"))
      (node (ref "R2") (pin "2") (pinfunction "2_2") (pintype "passive"))
      (node (ref "VREG12") (pin "1") (pinfunction "EN_1") (pintype "bidirectional"))
      (node (ref "VREG12") (pin "4") (pinfunction "VIN_4") (pintype "bidirectional"))
      (node (ref "VREG18") (pin "1") (pinfunction "EN_1") (pintype "bidirectional"))
      (node (ref "VREG18") (pin "4") (pinfunction "VIN_4") (pintype "bidirectional"))
      (node (ref "VREG33") (pin "1") (pinfunction "EN_1") (pintype "bidirectional"))
      (node (ref "VREG33") (pin "4") (pinfunction "VIN_4") (pintype "bidirectional"))
    )
    (net (code "5") (name "+5V_HOST") (class "Default")
      (node (ref "C1") (pin "A") (pinfunction "+_A") (pintype "passive"))
      (node (ref "C2") (pin "2") (pinfunction "2_2") (pintype "passive"))
      (node (ref "C3") (pin "2") (pinfunction "2_2") (pintype "passive"))
      (node (ref "CASCADE") (pin "1") (pinfunction "1_1") (pintype "passive"))
      (node (ref "HOST") (pin "VBUS") (pinfunction "VBUS_VBUS") (pintype "bidirectional"))
      (node (ref "PWRSW") (pin "1") (pinfunction "OUT_1") (pintype "bidirectional"))
    )
    (net (code "6") (name "AP_CTS") (class "Default")
      (node (ref "MCU") (pin "23") (pinfunction "USART2_CTS_23") (pintype "bidirectional"))
      (node (ref "R48") (pin "2") (pinfunction "2_2") (pintype "passive"))
      (node (ref "WIFI/BT") (pin "41") (pinfunction "UART_RTS#_41") (pintype "bidirectional"))
    )
    (net (code "7") (name "AP_RTS") (class "Default")
      (node (ref "MCU") (pin "24") (pinfunction "USART2_RTS_24") (pintype "bidirectional"))
      (node (ref "R45") (pin "2") (pinfunction "2_2") (pintype "passive"))
      (node (ref "WIFI/BT") (pin "44") (pinfunction "UART_CTS#_44") (pintype "bidirectional"))
    )
    (net (code "8") (name "AP_RXD") (class "Default")
      (node (ref "MCU") (pin "26") (pinfunction "USART2_RX_26") (pintype "bidirectional"))
      (node (ref "R47") (pin "2") (pinfunction "2_2") (pintype "passive"))
      (node (ref "WIFI/BT") (pin "42") (pinfunction "UART_TXD_42") (pintype "bidirectional"))
    )
    (net (code "9") (name "AP_TXD") (class "Default")
      (node (ref "MCU") (pin "25") (pinfunction "USART2_TX_25") (pintype "bidirectional"))
      (node (ref "R46") (pin "2") (pinfunction "2_2") (pintype "passive"))
      (node (ref "WIFI/BT") (pin "43") (pinfunction "UART_RXD_43") (pintype "bidirectional"))
    )
    (net (code "10") (name "AP_WAKE_BT") (class "Default")
      (node (ref "MCU") (pin "64") (pinfunction "PC7_64") (pintype "bidirectional"))
      (node (ref "WIFI/BT") (pin "6") (pinfunction "BT_WAKE_6") (pintype "bidirectional"))
    )
    (net (code "11") (name "AUDIO_L") (class "Default")
      (node (ref "FPGA") (pin "M12") (pinfunction "IO_L2P_CMPCLK_2_M12") (pintype "bidirectional"))
      (node (ref "R16") (pin "1") (pinfunction "1_1") (pintype "passive"))
    )
    (net (code "12") (name "AUDIO_R") (class "Default")
      (node (ref "FPGA") (pin "N12") (pinfunction "IO_L12P_D1_MISO2_2_N12") (pintype "bidirectional"))
      (node (ref "R50") (pin "1") (pinfunction "1_1") (pintype "passive"))
    )
    (net (code "13") (name "BOOT0") (class "Default")
      (node (ref "DFU") (pin "2") (pinfunction "B_2") (pintype "bidirectional"))
      (node (ref "MCU") (pin "94") (pinfunction "BOOT0_94") (pintype "bidirectional"))
      (node (ref "R35") (pin "1") (pinfunction "1_1") (pintype "passive"))
    )
    (net (code "14") (name "BOOT1") (class "Default")
      (node (ref "MCU") (pin "37") (pinfunction "BOOT1/PB2_37") (pintype "bidirectional"))
      (node (ref "PWRSW") (pin "4") (pinfunction "EN_4") (pintype "bidirectional"))
      (node (ref "R36") (pin "2") (pinfunction "2_2") (pintype "passive"))
    )
    (net (code "15") (name "BT_RST_N") (class "Default")
      (node (ref "MCU") (pin "63") (pinfunction "PC6_63") (pintype "bidirectional"))
      (node (ref "WIFI/BT") (pin "34") (pinfunction "BT_DIS#_34") (pintype "bidirectional"))
    )
    (net (code "16") (name "CLK_10M") (class "Default")
      (node (ref "FPGA") (pin "A9") (pinfunction "IO_L34N_GCLK18_0_A9") (pintype "bidirectional"))
      (node (ref "MCU") (pin "12") (pinfunction "OSC_IN_12") (pintype "bidirectional"))
      (node (ref "OSC10M") (pin "3") (pinfunction "OUT_3") (pintype "bidirectional"))
    )
    (net (code "17") (name "DDR2_VREF") (class "Default")
      (node (ref "C27") (pin "2") (pinfunction "2_2") (pintype "passive"))
      (node (ref "FPGA") (pin "A3") (pinfunction "IO_L83N_VREF_3_A3") (pintype "bidirectional"))
      (node (ref "FPGA") (pin "M3") (pinfunction "IO_L1N_VREF_3_M3") (pintype "bidirectional"))
      (node (ref "R61") (pin "1") (pinfunction "1_1") (pintype "passive"))
      (node (ref "R62") (pin "2") (pinfunction "2_2") (pintype "passive"))
      (node (ref "RAM") (pin "E2") (pinfunction "VREF_E2") (pintype "bidirectional"))
    )
    (net (code "18") (name "DEBUG_RX") (class "Default")
      (node (ref "JTAG-MCU") (pin "P13") (pinfunction "T_VCP_RX_P13") (pintype "bidirectional"))
      (node (ref "MCU") (pin "69") (pinfunction "USART1_RX_69") (pintype "bidirectional"))
    )
    (net (code "19") (name "DEBUG_TX") (class "Default")
      (node (ref "JTAG-MCU") (pin "P14") (pinfunction "T_VCP_TX_P14") (pintype "bidirectional"))
      (node (ref "MCU") (pin "92") (pinfunction "USART1_TX_92") (pintype "bidirectional"))
    )
    (net (code "20") (name "FPGA_CONFIG_CLK_I2S_CK") (class "Default")
      (node (ref "FPGA") (pin "R11") (pinfunction "IO_L1P_CCLK_2_R11") (pintype "bidirectional"))
      (node (ref "MCU") (pin "47") (pinfunction "SPI2_SCK/I2S2_CK_47") (pintype "bidirectional"))
    )
    (net (code "21") (name "FPGA_CONFIG_DIN_I2S_SD") (class "Default")
      (node (ref "FPGA") (pin "P10") (pinfunction "IO_L3P_D0_DIN_MISO_MISO1_2_P10") (pintype "bidirectional"))
      (node (ref "MCU") (pin "18") (pinfunction "SPI2_MOSI/I2S2_SD_18") (pintype "bidirectional"))
    )
    (net (code "22") (name "FPGA_CONFIG_DONE") (class "Default")
      (node (ref "FPGA") (pin "P13") (pinfunction "DONE_2_P13") (pintype "bidirectional"))
      (node (ref "MCU") (pin "36") (pinfunction "PB1_36") (pintype "bidirectional"))
    )
    (net (code "23") (name "FPGA_CONFIG_INIT_B") (class "Default")
      (node (ref "FPGA") (pin "R3") (pinfunction "IO_L65P_INIT_B_2_R3") (pintype "bidirectional"))
      (node (ref "MCU") (pin "17") (pinfunction "SPI2_MISO/I2S2EXT_SD_17") (pintype "bidirectional"))
      (node (ref "R30") (pin "1") (pinfunction "1_1") (pintype "passive"))
    )
    (net (code "24") (name "FPGA_CONFIG_PROGRAM_B") (class "Default")
      (node (ref "FPGA") (pin "T2") (pinfunction "PROGRAM_B_2_T2") (pintype "input"))
      (node (ref "MCU") (pin "34") (pinfunction "PC5_34") (pintype "bidirectional"))
      (node (ref "R29") (pin "2") (pinfunction "2_2") (pintype "passive"))
    )
    (net (code "25") (name "FPGA_I2S_WS") (class "Default")
      (node (ref "FPGA") (pin "H13") (pinfunction "IO_L39P_M1A3_1_H13") (pintype "bidirectional"))
      (node (ref "MCU") (pin "51") (pinfunction "SPI2_NSS/I2S2_WS_51") (pintype "bidirectional"))
    )
    (net (code "26") (name "FPGA_INT") (class "Default")
      (node (ref "FPGA") (pin "M14") (pinfunction "IO_L74N_DOUT_BUSY_1_M14") (pintype "bidirectional"))
      (node (ref "MCU") (pin "52") (pinfunction "PB13_52") (pintype "bidirectional"))
    )
    (net (code "27") (name "FSMC_A16") (class "Default")
      (node (ref "FPGA") (pin "R16") (pinfunction "IO_L49N_M1DQ11_1_R16") (pintype "bidirectional"))
      (node (ref "MCU") (pin "58") (pinfunction "A16_58") (pintype "bidirectional"))
    )
    (net (code "28") (name "FSMC_A17") (class "Default")
      (node (ref "FPGA") (pin "R15") (pinfunction "IO_L49P_M1DQ10_1_R15") (pintype "bidirectional"))
      (node (ref "MCU") (pin "59") (pinfunction "A17_59") (pintype "bidirectional"))
    )
    (net (code "29") (name "FSMC_A18") (class "Default")
      (node (ref "FPGA") (pin "R14") (pinfunction "IO_L50P_M1UDQS_1_R14") (pintype "bidirectional"))
      (node (ref "MCU") (pin "60") (pinfunction "A18_60") (pintype "bidirectional"))
    )
    (net (code "30") (name "FSMC_A19") (class "Default")
      (node (ref "FPGA") (pin "C16") (pinfunction "IO_L33N_A14_M1A4_1_C16") (pintype "bidirectional"))
      (node (ref "MCU") (pin "2") (pinfunction "A19_2") (pintype "bidirectional"))
    )
    (net (code "31") (name "FSMC_A20") (class "Default")
      (node (ref "FPGA") (pin "C15") (pinfunction "IO_L33P_A15_M1A10_1_C15") (pintype "bidirectional"))
      (node (ref "MCU") (pin "3") (pinfunction "A20_3") (pintype "bidirectional"))
    )
    (net (code "32") (name "FSMC_A21") (class "Default")
      (node (ref "FPGA") (pin "B16") (pinfunction "IO_L29N_A22_M1A14_1_B16") (pintype "bidirectional"))
      (node (ref "MCU") (pin "4") (pinfunction "A21_4") (pintype "bidirectional"))
    )
    (net (code "33") (name "FSMC_A22") (class "Default")
      (node (ref "FPGA") (pin "B15") (pinfunction "IO_L29P_A23_M1A13_1_B15") (pintype "bidirectional"))
      (node (ref "MCU") (pin "5") (pinfunction "A22_5") (pintype "bidirectional"))
    )
    (net (code "34") (name "FSMC_A23") (class "Default")
      (node (ref "FPGA") (pin "D14") (pinfunction "IO_L31P_A19_M1CKE_1_D14") (pintype "bidirectional"))
      (node (ref "MCU") (pin "1") (pinfunction "A23_1") (pintype "bidirectional"))
    )
    (net (code "35") (name "FSMC_CLK") (class "Default")
      (node (ref "FPGA") (pin "K14") (pinfunction "IO_L41N_GCLK8_M1CASN_1_K14") (pintype "bidirectional"))
      (node (ref "MCU") (pin "84") (pinfunction "CLK_84") (pintype "bidirectional"))
    )
    (net (code "36") (name "FSMC_D0") (class "Default")
      (node (ref "FPGA") (pin "T15") (pinfunction "IO_L50N_M1UDQSN_1_T15") (pintype "bidirectional"))
      (node (ref "MCU") (pin "61") (pinfunction "A0/D0_61") (pintype "bidirectional"))
    )
    (net (code "37") (name "FSMC_D1") (class "Default")
      (node (ref "FPGA") (pin "T14") (pinfunction "IO_L51P_M1DQ12_1_T14") (pintype "bidirectional"))
      (node (ref "MCU") (pin "62") (pinfunction "A1/D1_62") (pintype "bidirectional"))
    )
    (net (code "38") (name "FSMC_D2") (class "Default")
      (node (ref "FPGA") (pin "H15") (pinfunction "IO_L37P_A7_M1A0_1_H15") (pintype "bidirectional"))
      (node (ref "MCU") (pin "81") (pinfunction "A2/D2_81") (pintype "bidirectional"))
    )
    (net (code "39") (name "FSMC_D3") (class "Default")
      (node (ref "FPGA") (pin "G16") (pinfunction "IO_L36N_A8_M1BA1_1_G16") (pintype "bidirectional"))
      (node (ref "MCU") (pin "82") (pinfunction "A3/D3_82") (pintype "bidirectional"))
    )
    (net (code "40") (name "FSMC_D4") (class "Default")
      (node (ref "FPGA") (pin "H16") (pinfunction "IO_L37N_A6_M1A1_1_H16") (pintype "bidirectional"))
      (node (ref "MCU") (pin "38") (pinfunction "A4/D4_38") (pintype "bidirectional"))
    )
    (net (code "41") (name "FSMC_D5") (class "Default")
      (node (ref "FPGA") (pin "H14") (pinfunction "IO_L39N_M1ODT_1_H14") (pintype "bidirectional"))
      (node (ref "MCU") (pin "39") (pinfunction "A5/D5_39") (pintype "bidirectional"))
    )
    (net (code "42") (name "FSMC_D6") (class "Default")
      (node (ref "FPGA") (pin "K15") (pinfunction "IO_L44P_A3_M1DQ6_1_K15") (pintype "bidirectional"))
      (node (ref "MCU") (pin "40") (pinfunction "A6/D6_40") (pintype "bidirectional"))
    )
    (net (code "43") (name "FSMC_D7") (class "Default")
      (node (ref "FPGA") (pin "K16") (pinfunction "IO_L44N_A2_M1DQ7_1_K16") (pintype "bidirectional"))
      (node (ref "MCU") (pin "41") (pinfunction "A7/D7_41") (pintype "bidirectional"))
    )
    (net (code "44") (name "FSMC_D8") (class "Default")
      (node (ref "FPGA") (pin "L14") (pinfunction "IO_L47P_FWE_B_M1DQ0_1_L14") (pintype "bidirectional"))
      (node (ref "MCU") (pin "42") (pinfunction "A8/D8_42") (pintype "bidirectional"))
    )
    (net (code "45") (name "FSMC_D9") (class "Default")
      (node (ref "FPGA") (pin "L16") (pinfunction "IO_L47N_LDC_M1DQ1_1_L16") (pintype "bidirectional"))
      (node (ref "MCU") (pin "43") (pinfunction "A9/D9_43") (pintype "bidirectional"))
    )
    (net (code "46") (name "FSMC_D10") (class "Default")
      (node (ref "FPGA") (pin "M15") (pinfunction "IO_L46P_FCS_B_M1DQ2_1_M15") (pintype "bidirectional"))
      (node (ref "MCU") (pin "44") (pinfunction "A10/D10_44") (pintype "bidirectional"))
    )
    (net (code "47") (name "FSMC_D11") (class "Default")
      (node (ref "FPGA") (pin "M16") (pinfunction "IO_L46N_FOE_B_M1DQ3_1_M16") (pintype "bidirectional"))
      (node (ref "MCU") (pin "45") (pinfunction "A11/D11_45") (pintype "bidirectional"))
    )
    (net (code "48") (name "FSMC_D12") (class "Default")
      (node (ref "FPGA") (pin "N14") (pinfunction "IO_L45P_A1_M1LDQS_1_N14") (pintype "bidirectional"))
      (node (ref "MCU") (pin "46") (pinfunction "A12/D12_46") (pintype "bidirectional"))
    )
    (net (code "49") (name "FSMC_D13") (class "Default")
      (node (ref "FPGA") (pin "N16") (pinfunction "IO_L45N_A0_M1LDQSN_1_N16") (pintype "bidirectional"))
      (node (ref "MCU") (pin "55") (pinfunction "A13/D13_55") (pintype "bidirectional"))
    )
    (net (code "50") (name "FSMC_D14") (class "Default")
      (node (ref "FPGA") (pin "P16") (pinfunction "IO_L48N_M1DQ9_1_P16") (pintype "bidirectional"))
      (node (ref "MCU") (pin "56") (pinfunction "A14/D14_56") (pintype "bidirectional"))
    )
    (net (code "51") (name "FSMC_D15") (class "Default")
      (node (ref "FPGA") (pin "P15") (pinfunction "IO_L48P_HDC_M1DQ8_1_P15") (pintype "bidirectional"))
      (node (ref "MCU") (pin "57") (pinfunction "A15/D15_57") (pintype "bidirectional"))
    )
    (net (code "52") (name "FSMC_NBL0") (class "Default")
      (node (ref "FPGA") (pin "E15") (pinfunction "IO_L34P_A13_M1WE_1_E15") (pintype "bidirectional"))
      (node (ref "MCU") (pin "97") (pinfunction "NBL0_97") (pintype "bidirectional"))
    )
    (net (code "53") (name "FSMC_NBL1") (class "Default")
      (node (ref "FPGA") (pin "D16") (pinfunction "IO_L31N_A18_M1A12_1_D16") (pintype "bidirectional"))
      (node (ref "MCU") (pin "98") (pinfunction "NBL1_98") (pintype "bidirectional"))
    )
    (net (code "54") (name "FSMC_NE1") (class "Default")
      (node (ref "FPGA") (pin "F14") (pinfunction "IO_L32N_A16_M1A9_1_F14") (pintype "bidirectional"))
      (node (ref "MCU") (pin "88") (pinfunction "NE1_88") (pintype "bidirectional"))
    )
    (net (code "55") (name "FSMC_NL") (class "Default")
      (node (ref "FPGA") (pin "E16") (pinfunction "IO_L34N_A12_M1BA2_1_E16") (pintype "bidirectional"))
      (node (ref "MCU") (pin "93") (pinfunction "NL_93") (pintype "bidirectional"))
    )
    (net (code "56") (name "FSMC_NOE") (class "Default")
      (node (ref "FPGA") (pin "G14") (pinfunction "IO_L36P_A9_M1BA0_1_G14") (pintype "bidirectional"))
      (node (ref "MCU") (pin "85") (pinfunction "NOE_85") (pintype "bidirectional"))
    )
    (net (code "57") (name "FSMC_NWAIT") (class "Default")
      (node (ref "FPGA") (pin "F15") (pinfunction "IO_L35P_A11_M1A7_1_F15") (pintype "bidirectional"))
      (node (ref "MCU") (pin "87") (pinfunction "NWAIT_87") (pintype "bidirectional"))
    )
    (net (code "58") (name "FSMC_NWE") (class "Default")
      (node (ref "FPGA") (pin "F16") (pinfunction "IO_L35N_A10_M1A2_1_F16") (pintype "bidirectional"))
      (node (ref "MCU") (pin "86") (pinfunction "NWE_86") (pintype "bidirectional"))
    )
    (net (code "59") (name "GND") (class "Default")
      (node (ref "A/V") (pin "RING2") (pinfunction "GND_RING2") (pintype "bidirectional"))
      (node (ref "ACTIVITY") (pin "C") (pinfunction "C_C") (pintype "passive"))
      (node (ref "ANTENNA") (pin "GND") (pinfunction "GND_GND") (pintype "bidirectional"))
      (node (ref "BAT") (pin "GND") (pinfunction "-_GND") (pintype "power_in"))
      (node (ref "C1") (pin "C") (pinfunction "-_C") (pintype "passive"))
      (node (ref "C10") (pin "C") (pinfunction "-_C") (pintype "passive"))
      (node (ref "C11") (pin "C") (pinfunction "-_C") (pintype "passive"))
      (node (ref "C12") (pin "1") (pinfunction "1_1") (pintype "passive"))
      (node (ref "C13") (pin "2") (pinfunction "2_2") (pintype "passive"))
      (node (ref "C14") (pin "1") (pinfunction "1_1") (pintype "passive"))
      (node (ref "C15") (pin "1") (pinfunction "1_1") (pintype "passive"))
      (node (ref "C16") (pin "1") (pinfunction "1_1") (pintype "passive"))
      (node (ref "C17") (pin "1") (pinfunction "1_1") (pintype "passive"))
      (node (ref "C18") (pin "2") (pinfunction "2_2") (pintype "passive"))
      (node (ref "C19") (pin "1") (pinfunction "1_1") (pintype "passive"))
      (node (ref "C2") (pin "1") (pinfunction "1_1") (pintype "passive"))
      (node (ref "C20") (pin "1") (pinfunction "1_1") (pintype "passive"))
      (node (ref "C23") (pin "2") (pinfunction "2_2") (pintype "passive"))
      (node (ref "C24") (pin "1") (pinfunction "1_1") (pintype "passive"))
      (node (ref "C25") (pin "1") (pinfunction "1_1") (pintype "passive"))
      (node (ref "C26") (pin "1") (pinfunction "1_1") (pintype "passive"))
      (node (ref "C27") (pin "1") (pinfunction "1_1") (pintype "passive"))
      (node (ref "C28") (pin "1") (pinfunction "1_1") (pintype "passive"))
      (node (ref "C29") (pin "2") (pinfunction "2_2") (pintype "passive"))
      (node (ref "C3") (pin "1") (pinfunction "1_1") (pintype "passive"))
      (node (ref "C30") (pin "1") (pinfunction "1_1") (pintype "passive"))
      (node (ref "C31") (pin "2") (pinfunction "2_2") (pintype "passive"))
      (node (ref "C33") (pin "2") (pinfunction "2_2") (pintype "passive"))
      (node (ref "C36") (pin "1") (pinfunction "1_1") (pintype "passive"))
      (node (ref "C37") (pin "1") (pinfunction "1_1") (pintype "passive"))
      (node (ref "C38") (pin "1") (pinfunction "1_1") (pintype "passive"))
      (node (ref "C39") (pin "1") (pinfunction "1_1") (pintype "passive"))
      (node (ref "C4") (pin "1") (pinfunction "1_1") (pintype "passive"))
      (node (ref "C42") (pin "1") (pinfunction "1_1") (pintype "passive"))
      (node (ref "C43") (pin "1") (pinfunction "1_1") (pintype "passive"))
      (node (ref "C44") (pin "1") (pinfunction "1_1") (pintype "passive"))
      (node (ref "C45") (pin "1") (pinfunction "1_1") (pintype "passive"))
      (node (ref "C46") (pin "1") (pinfunction "1_1") (pintype "passive"))
      (node (ref "C47") (pin "1") (pinfunction "1_1") (pintype "passive"))
      (node (ref "C48") (pin "1") (pinfunction "1_1") (pintype "passive"))
      (node (ref "C49") (pin "1") (pinfunction "1_1") (pintype "passive"))
      (node (ref "C5") (pin "1") (pinfunction "1_1") (pintype "passive"))
      (node (ref "C50") (pin "1") (pinfunction "1_1") (pintype "passive"))
      (node (ref "C54") (pin "1") (pinfunction "1_1") (pintype "passive"))
      (node (ref "C58") (pin "1") (pinfunction "1_1") (pintype "passive"))
      (node (ref "C59") (pin "1") (pinfunction "1_1") (pintype "passive"))
      (node (ref "C6") (pin "1") (pinfunction "1_1") (pintype "passive"))
      (node (ref "C7") (pin "1") (pinfunction "1_1") (pintype "passive"))
      (node (ref "C8") (pin "2") (pinfunction "2_2") (pintype "passive"))
      (node (ref "C9") (pin "C") (pinfunction "-_C") (pintype "passive"))
      (node (ref "CASCADE") (pin "3") (pinfunction "3_3") (pintype "passive"))
      (node (ref "DEVICE") (pin "5") (pinfunction "GND_5") (pintype "bidirectional"))
      (node (ref "FPGA") (pin "A1") (pinfunction "GND_A1") (pintype "power_in"))
      (node (ref "FPGA") (pin "A16") (pinfunction "GND_A16") (pintype "power_in"))
      (node (ref "FPGA") (pin "B11") (pinfunction "GND_B11") (pintype "power_in"))
      (node (ref "FPGA") (pin "B7") (pinfunction "GND_B7") (pintype "power_in"))
      (node (ref "FPGA") (pin "C4") (pinfunction "IO_L1P_HSWAPEN_0_C4") (pintype "bidirectional"))
      (node (ref "FPGA") (pin "D13") (pinfunction "GND_D13") (pintype "power_in"))
      (node (ref "FPGA") (pin "D4") (pinfunction "GND_D4") (pintype "power_in"))
      (node (ref "FPGA") (pin "E9") (pinfunction "GND_E9") (pintype "power_in"))
      (node (ref "FPGA") (pin "G15") (pinfunction "GND_G15") (pintype "power_in"))
      (node (ref "FPGA") (pin "G2") (pinfunction "GND_G2") (pintype "power_in"))
      (node (ref "FPGA") (pin "G8") (pinfunction "GND_G8") (pintype "power_in"))
      (node (ref "FPGA") (pin "H12") (pinfunction "GND_H12") (pintype "power_in"))
      (node (ref "FPGA") (pin "H7") (pinfunction "GND_H7") (pintype "power_in"))
      (node (ref "FPGA") (pin "H9") (pinfunction "GND_H9") (pintype "power_in"))
      (node (ref "FPGA") (pin "J5") (pinfunction "GND_J5") (pintype "power_in"))
      (node (ref "FPGA") (pin "J8") (pinfunction "GND_J8") (pintype "power_in"))
      (node (ref "FPGA") (pin "K7") (pinfunction "GND_K7") (pintype "power_in"))
      (node (ref "FPGA") (pin "K9") (pinfunction "GND_K9") (pintype "power_in"))
      (node (ref "FPGA") (pin "L15") (pinfunction "GND_L15") (pintype "power_in"))
      (node (ref "FPGA") (pin "L2") (pinfunction "GND_L2") (pintype "power_in"))
      (node (ref "FPGA") (pin "M8") (pinfunction "GND_M8") (pintype "power_in"))
      (node (ref "FPGA") (pin "N13") (pinfunction "GND_N13") (pintype "power_in"))
      (node (ref "FPGA") (pin "P14") (pinfunction "SUSPEND_P14") (pintype "input"))
      (node (ref "FPGA") (pin "P3") (pinfunction "GND_P3") (pintype "power_in"))
      (node (ref "FPGA") (pin "R10") (pinfunction "GND_R10") (pintype "power_in"))
      (node (ref "FPGA") (pin "R6") (pinfunction "GND_R6") (pintype "power_in"))
      (node (ref "FPGA") (pin "T1") (pinfunction "GND_T1") (pintype "power_in"))
      (node (ref "FPGA") (pin "T16") (pinfunction "GND_T16") (pintype "power_in"))
      (node (ref "GPIO") (pin "14") (pinfunction "14_14") (pintype "passive"))
      (node (ref "GPIO") (pin "20") (pinfunction "20_20") (pintype "passive"))
      (node (ref "GPIO") (pin "25") (pinfunction "25_25") (pintype "passive"))
      (node (ref "GPIO") (pin "30") (pinfunction "30_30") (pintype "passive"))
      (node (ref "GPIO") (pin "34") (pinfunction "34_34") (pintype "passive"))
      (node (ref "GPIO") (pin "39") (pinfunction "39_39") (pintype "passive"))
      (node (ref "GPIO") (pin "6") (pinfunction "6_6") (pintype "passive"))
      (node (ref "GPIO") (pin "9") (pinfunction "9_9") (pintype "passive"))
      (node (ref "HOST") (pin "GND") (pinfunction "GND_GND") (pintype "bidirectional"))
      (node (ref "HOST") (pin "SH1") (pinfunction "SH1_SH1") (pintype "bidirectional"))
      (node (ref "HOST") (pin "SH2") (pinfunction "SH2_SH2") (pintype "bidirectional"))
      (node (ref "JTAG-FPGA") (pin "P11") (pinfunction "GND_P11") (pintype "bidirectional"))
      (node (ref "JTAG-FPGA") (pin "P3") (pinfunction "GND_P3") (pintype "bidirectional"))
      (node (ref "JTAG-FPGA") (pin "P5") (pinfunction "GND_P5") (pintype "bidirectional"))
      (node (ref "JTAG-FPGA") (pin "P7") (pinfunction "GND_P7") (pintype "bidirectional"))
      (node (ref "JTAG-FPGA") (pin "P9") (pinfunction "GND_P9") (pintype "bidirectional"))
      (node (ref "JTAG-MCU") (pin "P5") (pinfunction "GND_P5") (pintype "bidirectional"))
      (node (ref "JTAG-MCU") (pin "P7") (pinfunction "GND_P7") (pintype "bidirectional"))
      (node (ref "LVDS") (pin "P11") (pinfunction "TMDS_CLK_SHLD_P11") (pintype "bidirectional"))
      (node (ref "LVDS") (pin "P17") (pinfunction "GND_P17") (pintype "bidirectional"))
      (node (ref "LVDS") (pin "P2") (pinfunction "TMDS_D2_SHLD_P2") (pintype "bidirectional"))
      (node (ref "LVDS") (pin "P5") (pinfunction "TMDS_D1_SHLD_P5") (pintype "bidirectional"))
      (node (ref "LVDS") (pin "P8") (pinfunction "TMDS_D0_SHLD_P8") (pintype "bidirectional"))
      (node (ref "LVDS") (pin "SH1") (pinfunction "SH1_SH1") (pintype "bidirectional"))
      (node (ref "LVDS") (pin "SH2") (pinfunction "SH2_SH2") (pintype "bidirectional"))
      (node (ref "LVDS") (pin "SH3") (pinfunction "SH3_SH3") (pintype "bidirectional"))
      (node (ref "LVDS") (pin "SH4") (pinfunction "SH4_SH4") (pintype "bidirectional"))
      (node (ref "MCU") (pin "10") (pinfunction "VSS_10") (pintype "bidirectional"))
      (node (ref "MCU") (pin "20") (pinfunction "VSSA_20") (pintype "bidirectional"))
      (node (ref "MCU") (pin "27") (pinfunction "VSS_27") (pintype "bidirectional"))
      (node (ref "MCU") (pin "74") (pinfunction "VSS_74") (pintype "bidirectional"))
      (node (ref "MCU") (pin "99") (pinfunction "VSS_99") (pintype "bidirectional"))
      (node (ref "MICROSD") (pin "G1") (pinfunction "GND_G1") (pintype "bidirectional"))
      (node (ref "MICROSD") (pin "G2") (pinfunction "GND_G2") (pintype "bidirectional"))
      (node (ref "MICROSD") (pin "G3") (pinfunction "GND_G3") (pintype "bidirectional"))
      (node (ref "MICROSD") (pin "G4") (pinfunction "GND_G4") (pintype "bidirectional"))
      (node (ref "MICROSD") (pin "P6") (pinfunction "VSS_P6") (pintype "bidirectional"))
      (node (ref "OSC10M") (pin "2") (pinfunction "GND_2") (pintype "bidirectional"))
      (node (ref "PIXEL") (pin "3-GND") (pinfunction "GND_3-GND") (pintype "bidirectional"))
      (node (ref "PWRSW") (pin "2") (pinfunction "GND_2") (pintype "bidirectional"))
      (node (ref "R13") (pin "1") (pinfunction "1_1") (pintype "passive"))
      (node (ref "R14") (pin "1") (pinfunction "1_1") (pintype "passive"))
      (node (ref "R26") (pin "1") (pinfunction "1_1") (pintype "passive"))
      (node (ref "R27") (pin "2") (pinfunction "2_2") (pintype "passive"))
      (node (ref "R28") (pin "1") (pinfunction "1_1") (pintype "passive"))
      (node (ref "R35") (pin "2") (pinfunction "2_2") (pintype "passive"))
      (node (ref "R36") (pin "1") (pinfunction "1_1") (pintype "passive"))
      (node (ref "R60") (pin "1") (pinfunction "1_1") (pintype "passive"))
      (node (ref "R62") (pin "1") (pinfunction "1_1") (pintype "passive"))
      (node (ref "R63") (pin "1") (pinfunction "1_1") (pintype "passive"))
      (node (ref "R64") (pin "2") (pinfunction "2_2") (pintype "passive"))
      (node (ref "R66") (pin "1") (pinfunction "1_1") (pintype "passive"))
      (node (ref "RAM") (pin "A3") (pinfunction "VSS_A3") (pintype "bidirectional"))
      (node (ref "RAM") (pin "A7") (pinfunction "VSSQ_A7") (pintype "bidirectional"))
      (node (ref "RAM") (pin "B2") (pinfunction "VSSQ_B2") (pintype "bidirectional"))
      (node (ref "RAM") (pin "B8") (pinfunction "VSSQ_B8") (pintype "bidirectional"))
      (node (ref "RAM") (pin "D2") (pinfunction "VSSQ_D2") (pintype "bidirectional"))
      (node (ref "RAM") (pin "D8") (pinfunction "VSSQ_D8") (pintype "bidirectional"))
      (node (ref "RAM") (pin "E3") (pinfunction "VSS_E3") (pintype "bidirectional"))
      (node (ref "RAM") (pin "E7") (pinfunction "VSSDL_E7") (pintype "bidirectional"))
      (node (ref "RAM") (pin "J1") (pinfunction "VSS_J1") (pintype "bidirectional"))
      (node (ref "RAM") (pin "K9") (pinfunction "VSS_K9") (pintype "bidirectional"))
      (node (ref "RESET") (pin "1") (pinfunction "A_1") (pintype "bidirectional"))
      (node (ref "VREG12") (pin "2") (pinfunction "GND_2") (pintype "bidirectional"))
      (node (ref "VREG18") (pin "2") (pinfunction "GND_2") (pintype "bidirectional"))
      (node (ref "VREG33") (pin "2") (pinfunction "GND_2") (pintype "bidirectional"))
      (node (ref "WIFI/BT") (pin "1") (pinfunction "GND_1") (pintype "bidirectional"))
      (node (ref "WIFI/BT") (pin "20") (pinfunction "GND_20") (pintype "bidirectional"))
      (node (ref "WIFI/BT") (pin "31") (pinfunction "GND_31") (pintype "bidirectional"))
      (node (ref "WIFI/BT") (pin "33") (pinfunction "GND_33") (pintype "bidirectional"))
      (node (ref "WIFI/BT") (pin "36") (pinfunction "GND_36") (pintype "bidirectional"))
    )
    (net (code "60") (name "GPIO00") (class "Default")
      (node (ref "FPGA") (pin "A5") (pinfunction "IO_L2N_0_A5") (pintype "bidirectional"))
      (node (ref "GPIO") (pin "11") (pinfunction "11_11") (pintype "passive"))
    )
    (net (code "61") (name "GPIO01") (class "Default")
      (node (ref "FPGA") (pin "C6") (pinfunction "IO_L7N_0_C6") (pintype "bidirectional"))
      (node (ref "GPIO") (pin "12") (pinfunction "12_12") (pintype "passive"))
    )
    (net (code "62") (name "GPIO02") (class "Default")
      (node (ref "FPGA") (pin "B6") (pinfunction "IO_L4P_0_B6") (pintype "bidirectional"))
      (node (ref "GPIO") (pin "13") (pinfunction "13_13") (pintype "passive"))
    )
    (net (code "63") (name "GPIO03") (class "Default")
      (node (ref "FPGA") (pin "A6") (pinfunction "IO_L4N_0_A6") (pintype "bidirectional"))
      (node (ref "GPIO") (pin "15") (pinfunction "15_15") (pintype "passive"))
    )
    (net (code "64") (name "GPIO04") (class "Default")
      (node (ref "FPGA") (pin "C7") (pinfunction "IO_L6P_0_C7") (pintype "bidirectional"))
      (node (ref "GPIO") (pin "16") (pinfunction "16_16") (pintype "passive"))
    )
    (net (code "65") (name "GPIO05") (class "Default")
      (node (ref "FPGA") (pin "A7") (pinfunction "IO_L6N_0_A7") (pintype "bidirectional"))
      (node (ref "GPIO") (pin "18") (pinfunction "18_18") (pintype "passive"))
    )
    (net (code "66") (name "GPIO06") (class "Default")
      (node (ref "FPGA") (pin "A8") (pinfunction "IO_L33N_0_A8") (pintype "bidirectional"))
      (node (ref "GPIO") (pin "22") (pinfunction "22_22") (pintype "passive"))
    )
    (net (code "67") (name "GPIO07") (class "Default")
      (node (ref "FPGA") (pin "A4") (pinfunction "IO_L1N_VREF_0_A4") (pintype "bidirectional"))
      (node (ref "GPIO") (pin "7") (pinfunction "7_7") (pintype "passive"))
      (node (ref "MCU") (pin "15") (pinfunction "ADC123_IN10_15") (pintype "bidirectional"))
    )
    (net (code "68") (name "GPIO08") (class "Default")
      (node (ref "FPGA") (pin "C5") (pinfunction "IO_L3N_0_C5") (pintype "bidirectional"))
      (node (ref "GPIO") (pin "3") (pinfunction "3_3") (pintype "passive"))
    )
    (net (code "69") (name "GPIO09") (class "Default")
      (node (ref "FPGA") (pin "D5") (pinfunction "IO_L3P_0_D5") (pintype "bidirectional"))
      (node (ref "GPIO") (pin "5") (pinfunction "5_5") (pintype "passive"))
    )
    (net (code "70") (name "GPIO10") (class "Default")
      (node (ref "FPGA") (pin "C9") (pinfunction "IO_L34P_GCLK19_0_C9") (pintype "bidirectional"))
      (node (ref "GPIO") (pin "24") (pinfunction "24_24") (pintype "passive"))
    )
    (net (code "71") (name "GPIO11") (class "Default")
      (node (ref "FPGA") (pin "D9") (pinfunction "IO_L40N_0_D9") (pintype "bidirectional"))
      (node (ref "GPIO") (pin "26") (pinfunction "26_26") (pintype "passive"))
    )
    (net (code "72") (name "GPIO12") (class "Default")
      (node (ref "FPGA") (pin "C8") (pinfunction "IO_L38N_VREF_0_C8") (pintype "bidirectional"))
      (node (ref "GPIO") (pin "19") (pinfunction "19_19") (pintype "passive"))
    )
    (net (code "73") (name "GPIO13") (class "Default")
      (node (ref "FPGA") (pin "D8") (pinfunction "IO_L38P_0_D8") (pintype "bidirectional"))
      (node (ref "GPIO") (pin "21") (pinfunction "21_21") (pintype "passive"))
    )
    (net (code "74") (name "GPIO14") (class "Default")
      (node (ref "FPGA") (pin "B8") (pinfunction "IO_L33P_0_B8") (pintype "bidirectional"))
      (node (ref "GPIO") (pin "23") (pinfunction "23_23") (pintype "passive"))
    )
    (net (code "75") (name "GPIO15") (class "Default")
      (node (ref "FPGA") (pin "B5") (pinfunction "IO_L2P_0_B5") (pintype "bidirectional"))
      (node (ref "GPIO") (pin "8") (pinfunction "8_8") (pintype "passive"))
    )
    (net (code "76") (name "GPIO16") (class "Default")
      (node (ref "FPGA") (pin "D6") (pinfunction "IO_L7P_0_D6") (pintype "bidirectional"))
      (node (ref "GPIO") (pin "10") (pinfunction "10_10") (pintype "passive"))
    )
    (net (code "77") (name "GPIO21") (class "Default")
      (node (ref "FPGA") (pin "A11") (pinfunction "IO_L39N_0_A11") (pintype "bidirectional"))
      (node (ref "GPIO") (pin "29") (pinfunction "29_29") (pintype "passive"))
    )
    (net (code "78") (name "GPIO22") (class "Default")
      (node (ref "FPGA") (pin "A12") (pinfunction "IO_L62N_VREF_0_A12") (pintype "bidirectional"))
      (node (ref "GPIO") (pin "31") (pinfunction "31_31") (pintype "passive"))
    )
    (net (code "79") (name "GPIO23") (class "Default")
      (node (ref "FPGA") (pin "B12") (pinfunction "IO_L62P_0_B12") (pintype "bidirectional"))
      (node (ref "GPIO") (pin "33") (pinfunction "33_33") (pintype "passive"))
      (node (ref "MCU") (pin "16") (pinfunction "ADC123_IN11_16") (pintype "bidirectional"))
    )
    (net (code "80") (name "GPIO24") (class "Default")
      (node (ref "FPGA") (pin "A14") (pinfunction "IO_L65N_SCP2_0_A14") (pintype "bidirectional"))
      (node (ref "GPIO") (pin "35") (pinfunction "35_35") (pintype "passive"))
    )
    (net (code "81") (name "GPIO25") (class "Default")
      (node (ref "FPGA") (pin "C13") (pinfunction "IO_L63P_SCP7_0_C13") (pintype "bidirectional"))
      (node (ref "GPIO") (pin "37") (pinfunction "37_37") (pintype "passive"))
    )
    (net (code "82") (name "GPIO26") (class "Default")
      (node (ref "FPGA") (pin "C11") (pinfunction "IO_L39P_0_C11") (pintype "bidirectional"))
      (node (ref "GPIO") (pin "32") (pinfunction "32_32") (pintype "passive"))
    )
    (net (code "83") (name "GPIO27") (class "Default")
      (node (ref "FPGA") (pin "A13") (pinfunction "IO_L63N_SCP6_0_A13") (pintype "bidirectional"))
      (node (ref "GPIO") (pin "36") (pinfunction "36_36") (pintype "passive"))
    )
    (net (code "84") (name "GPIO28") (class "Default")
      (node (ref "FPGA") (pin "B14") (pinfunction "IO_L65P_SCP3_0_B14") (pintype "bidirectional"))
      (node (ref "GPIO") (pin "38") (pinfunction "38_38") (pintype "passive"))
    )
    (net (code "85") (name "GPIO29") (class "Default")
      (node (ref "FPGA") (pin "D12") (pinfunction "IO_L66N_SCP0_0_D12") (pintype "bidirectional"))
      (node (ref "GPIO") (pin "40") (pinfunction "40_40") (pintype "passive"))
    )
    (net (code "86") (name "ID_SC") (class "Default")
      (node (ref "FPGA") (pin "C10") (pinfunction "IO_L37N_GCLK12_0_C10") (pintype "bidirectional"))
      (node (ref "GPIO") (pin "28") (pinfunction "28_28") (pintype "passive"))
    )
    (net (code "87") (name "ID_SD") (class "Default")
      (node (ref "FPGA") (pin "A10") (pinfunction "IO_L35N_GCLK16_0_A10") (pintype "bidirectional"))
      (node (ref "GPIO") (pin "27") (pinfunction "27_27") (pintype "passive"))
    )
    (net (code "88") (name "JTAG_FPGA_TCK") (class "Default")
      (node (ref "FPGA") (pin "C14") (pinfunction "TCK_C14") (pintype "input"))
      (node (ref "JTAG-FPGA") (pin "P6") (pinfunction "TCK_P6") (pintype "bidirectional"))
    )
    (net (code "89") (name "JTAG_FPGA_TDI") (class "Default")
      (node (ref "FPGA") (pin "C12") (pinfunction "TDI_C12") (pintype "input"))
      (node (ref "JTAG-FPGA") (pin "P10") (pinfunction "TDI_P10") (pintype "bidirectional"))
      (node (ref "R20") (pin "1") (pinfunction "1_1") (pintype "passive"))
    )
    (net (code "90") (name "JTAG_FPGA_TDO") (class "Default")
      (node (ref "FPGA") (pin "E14") (pinfunction "TDO_E14") (pintype "output"))
      (node (ref "JTAG-FPGA") (pin "P8") (pinfunction "TDO_P8") (pintype "bidirectional"))
    )
    (net (code "91") (name "JTAG_FPGA_TMS") (class "Default")
      (node (ref "FPGA") (pin "A15") (pinfunction "TMS_A15") (pintype "input"))
      (node (ref "JTAG-FPGA") (pin "P4") (pinfunction "TMS_P4") (pintype "bidirectional"))
      (node (ref "R1") (pin "1") (pinfunction "1_1") (pintype "passive"))
    )
    (net (code "92") (name "JTAG_MCU_TCK") (class "Default")
      (node (ref "JTAG-MCU") (pin "P6") (pinfunction "T_JCLK_P6") (pintype "bidirectional"))
      (node (ref "MCU") (pin "76") (pinfunction "TCK/SWCLK_76") (pintype "bidirectional"))
    )
    (net (code "93") (name "JTAG_MCU_TDI") (class "Default")
      (node (ref "JTAG-MCU") (pin "P10") (pinfunction "T_JTDI_P10") (pintype "bidirectional"))
      (node (ref "MCU") (pin "77") (pinfunction "TDI_77") (pintype "bidirectional"))
    )
    (net (code "94") (name "JTAG_MCU_TDO") (class "Default")
      (node (ref "JTAG-MCU") (pin "P8") (pinfunction "T_JTDO_P8") (pintype "bidirectional"))
      (node (ref "MCU") (pin "89") (pinfunction "TDO/SWO_89") (pintype "bidirectional"))
    )
    (net (code "95") (name "JTAG_MCU_TMS") (class "Default")
      (node (ref "JTAG-MCU") (pin "P4") (pinfunction "T_JTMS_P4") (pintype "bidirectional"))
      (node (ref "MCU") (pin "72") (pinfunction "TMS/SWDIO_72") (pintype "bidirectional"))
    )
    (net (code "96") (name "LED_ACT") (class "Default")
      (node (ref "MCU") (pin "35") (pinfunction "PB0_35") (pintype "bidirectional"))
      (node (ref "R3") (pin "1") (pinfunction "1_1") (pintype "passive"))
    )
    (net (code "97") (name "M3A0") (class "Default")
      (node (ref "FPGA") (pin "K5") (pinfunction "IO_L47P_M3A0_3_K5") (pintype "bidirectional"))
      (node (ref "RAM") (pin "H8") (pinfunction "A0_H8") (pintype "bidirectional"))
    )
    (net (code "98") (name "M3A1") (class "Default")
      (node (ref "FPGA") (pin "K6") (pinfunction "IO_L47N_M3A1_3_K6") (pintype "bidirectional"))
      (node (ref "RAM") (pin "H3") (pinfunction "A1_H3") (pintype "bidirectional"))
    )
    (net (code "99") (name "M3A2") (class "Default")
      (node (ref "FPGA") (pin "D1") (pinfunction "IO_L49N_M3A2_3_D1") (pintype "bidirectional"))
      (node (ref "RAM") (pin "H7") (pinfunction "A2_H7") (pintype "bidirectional"))
    )
    (net (code "100") (name "M3A3") (class "Default")
      (node (ref "FPGA") (pin "L4") (pinfunction "IO_L45P_M3A3_3_L4") (pintype "bidirectional"))
      (node (ref "RAM") (pin "J2") (pinfunction "A3_J2") (pintype "bidirectional"))
    )
    (net (code "101") (name "M3A4") (class "Default")
      (node (ref "FPGA") (pin "G5") (pinfunction "IO_L51N_M3A4_3_G5") (pintype "bidirectional"))
      (node (ref "RAM") (pin "J8") (pinfunction "A4_J8") (pintype "bidirectional"))
    )
    (net (code "102") (name "M3A5") (class "Default")
      (node (ref "FPGA") (pin "H4") (pinfunction "IO_L44P_GCLK21_M3A5_3_H4") (pintype "bidirectional"))
      (node (ref "RAM") (pin "J3") (pinfunction "A5_J3") (pintype "bidirectional"))
    )
    (net (code "103") (name "M3A6") (class "Default")
      (node (ref "FPGA") (pin "H3") (pinfunction "IO_L44N_GCLK20_M3A6_3_H3") (pintype "bidirectional"))
      (node (ref "RAM") (pin "J7") (pinfunction "A6_J7") (pintype "bidirectional"))
    )
    (net (code "104") (name "M3A7") (class "Default")
      (node (ref "FPGA") (pin "D3") (pinfunction "IO_L49P_M3A7_3_D3") (pintype "bidirectional"))
      (node (ref "RAM") (pin "K2") (pinfunction "A7_K2") (pintype "bidirectional"))
    )
    (net (code "105") (name "M3A8") (class "Default")
      (node (ref "FPGA") (pin "B2") (pinfunction "IO_L52P_M3A8_3_B2") (pintype "bidirectional"))
      (node (ref "RAM") (pin "K8") (pinfunction "A8_K8") (pintype "bidirectional"))
    )
    (net (code "106") (name "M3A9") (class "Default")
      (node (ref "FPGA") (pin "A2") (pinfunction "IO_L52N_M3A9_3_A2") (pintype "bidirectional"))
      (node (ref "RAM") (pin "K3") (pinfunction "A9_K3") (pintype "bidirectional"))
    )
    (net (code "107") (name "M3A10") (class "Default")
      (node (ref "FPGA") (pin "G6") (pinfunction "IO_L51P_M3A10_3_G6") (pintype "bidirectional"))
      (node (ref "RAM") (pin "H2") (pinfunction "A10_H2") (pintype "bidirectional"))
    )
    (net (code "108") (name "M3A11") (class "Default")
      (node (ref "FPGA") (pin "E3") (pinfunction "IO_L54N_M3A11_3_E3") (pintype "bidirectional"))
      (node (ref "RAM") (pin "K7") (pinfunction "A11_K7") (pintype "bidirectional"))
    )
    (net (code "109") (name "M3A12") (class "Default")
      (node (ref "FPGA") (pin "F3") (pinfunction "IO_L53N_M3A12_3_F3") (pintype "bidirectional"))
      (node (ref "RAM") (pin "L2") (pinfunction "A12_L2") (pintype "bidirectional"))
    )
    (net (code "110") (name "M3A13") (class "Default")
      (node (ref "FPGA") (pin "F6") (pinfunction "IO_L55P_M3A13_3_F6") (pintype "bidirectional"))
      (node (ref "RAM") (pin "L8") (pinfunction "A13_L8") (pintype "bidirectional"))
    )
    (net (code "111") (name "M3A14") (class "Default")
      (node (ref "FPGA") (pin "F5") (pinfunction "IO_L55N_M3A14_3_F5") (pintype "bidirectional"))
      (node (ref "RAM") (pin "L3") (pinfunction "RFU/A14_L3") (pintype "bidirectional"))
    )
    (net (code "112") (name "M3BA0") (class "Default")
      (node (ref "FPGA") (pin "C3") (pinfunction "IO_L48P_M3BA0_3_C3") (pintype "bidirectional"))
      (node (ref "RAM") (pin "G2") (pinfunction "BA0_G2") (pintype "bidirectional"))
    )
    (net (code "113") (name "M3BA1") (class "Default")
      (node (ref "FPGA") (pin "C2") (pinfunction "IO_L48N_M3BA1_3_C2") (pintype "bidirectional"))
      (node (ref "RAM") (pin "G3") (pinfunction "BA1_G3") (pintype "bidirectional"))
    )
    (net (code "114") (name "M3BA2") (class "Default")
      (node (ref "FPGA") (pin "B1") (pinfunction "IO_L50N_M3BA2_3_B1") (pintype "bidirectional"))
      (node (ref "RAM") (pin "G1") (pinfunction "BA2_G1") (pintype "bidirectional"))
    )
    (net (code "115") (name "M3CASN") (class "Default")
      (node (ref "FPGA") (pin "H5") (pinfunction "IO_L43N_GCLK22_IRDY2_M3CASN_3_H5") (pintype "bidirectional"))
      (node (ref "RAM") (pin "G7") (pinfunction "CAS#_G7") (pintype "bidirectional"))
    )
    (net (code "116") (name "M3CKE") (class "Default")
      (node (ref "FPGA") (pin "F4") (pinfunction "IO_L53P_M3CKE_3_F4") (pintype "bidirectional"))
      (node (ref "R28") (pin "2") (pinfunction "2_2") (pintype "passive"))
      (node (ref "RAM") (pin "F2") (pinfunction "CKE_F2") (pintype "bidirectional"))
    )
    (net (code "117") (name "M3CLK") (class "Default")
      (node (ref "FPGA") (pin "E2") (pinfunction "IO_L46P_M3CLK_3_E2") (pintype "bidirectional"))
      (node (ref "RAM") (pin "E8") (pinfunction "CK_E8") (pintype "bidirectional"))
    )
    (net (code "118") (name "M3CLKN") (class "Default")
      (node (ref "FPGA") (pin "E1") (pinfunction "IO_L46N_M3CLKN_3_E1") (pintype "bidirectional"))
      (node (ref "RAM") (pin "F8") (pinfunction "CK#_F8") (pintype "bidirectional"))
    )
    (net (code "119") (name "M3CSN") (class "Default")
      (node (ref "FPGA") (pin "M4") (pinfunction "IO_L1P_3_M4") (pintype "bidirectional"))
      (node (ref "RAM") (pin "G8") (pinfunction "CS#_G8") (pintype "bidirectional"))
    )
    (net (code "120") (name "M3DQ0") (class "Default")
      (node (ref "FPGA") (pin "K2") (pinfunction "IO_L37P_M3DQ0_3_K2") (pintype "bidirectional"))
      (node (ref "RAM") (pin "B1") (pinfunction "DQ6_B1") (pintype "bidirectional"))
    )
    (net (code "121") (name "M3DQ1") (class "Default")
      (node (ref "FPGA") (pin "K1") (pinfunction "IO_L37N_M3DQ1_3_K1") (pintype "bidirectional"))
      (node (ref "RAM") (pin "B9") (pinfunction "DQ7_B9") (pintype "bidirectional"))
    )
    (net (code "122") (name "M3DQ2") (class "Default")
      (node (ref "FPGA") (pin "J3") (pinfunction "IO_L38P_M3DQ2_3_J3") (pintype "bidirectional"))
      (node (ref "RAM") (pin "C2") (pinfunction "DQ1_C2") (pintype "bidirectional"))
    )
    (net (code "123") (name "M3DQ3") (class "Default")
      (node (ref "FPGA") (pin "J1") (pinfunction "IO_L38N_M3DQ3_3_J1") (pintype "bidirectional"))
      (node (ref "RAM") (pin "C8") (pinfunction "DQ0_C8") (pintype "bidirectional"))
    )
    (net (code "124") (name "M3DQ4") (class "Default")
      (node (ref "FPGA") (pin "F2") (pinfunction "IO_L41P_GCLK27_M3DQ4_3_F2") (pintype "bidirectional"))
      (node (ref "RAM") (pin "D7") (pinfunction "DQ2_D7") (pintype "bidirectional"))
    )
    (net (code "125") (name "M3DQ5") (class "Default")
      (node (ref "FPGA") (pin "F1") (pinfunction "IO_L41N_GCLK26_M3DQ5_3_F1") (pintype "bidirectional"))
      (node (ref "RAM") (pin "D9") (pinfunction "DQ5_D9") (pintype "bidirectional"))
    )
    (net (code "126") (name "M3DQ6") (class "Default")
      (node (ref "FPGA") (pin "G3") (pinfunction "IO_L40P_M3DQ6_3_G3") (pintype "bidirectional"))
      (node (ref "RAM") (pin "D1") (pinfunction "DQ4_D1") (pintype "bidirectional"))
    )
    (net (code "127") (name "M3DQ7") (class "Default")
      (node (ref "FPGA") (pin "G1") (pinfunction "IO_L40N_M3DQ7_3_G1") (pintype "bidirectional"))
      (node (ref "RAM") (pin "D3") (pinfunction "DQ3_D3") (pintype "bidirectional"))
    )
    (net (code "128") (name "M3LDM") (class "Default")
      (node (ref "FPGA") (pin "J4") (pinfunction "IO_L42N_GCLK24_M3LDM_3_J4") (pintype "bidirectional"))
      (node (ref "RAM") (pin "B3") (pinfunction "DM/RDQS_B3") (pintype "bidirectional"))
    )
    (net (code "129") (name "M3LDQS_N") (class "Default")
      (node (ref "FPGA") (pin "H1") (pinfunction "IO_L39N_M3LDQSN_3_H1") (pintype "bidirectional"))
      (node (ref "RAM") (pin "A8") (pinfunction "DQS#_A8") (pintype "bidirectional"))
    )
    (net (code "130") (name "M3LDQS_P") (class "Default")
      (node (ref "FPGA") (pin "H2") (pinfunction "IO_L39P_M3LDQS_3_H2") (pintype "bidirectional"))
      (node (ref "RAM") (pin "B7") (pinfunction "DQS_B7") (pintype "bidirectional"))
    )
    (net (code "131") (name "M3ODT") (class "Default")
      (node (ref "FPGA") (pin "L5") (pinfunction "IO_L45N_M3ODT_3_L5") (pintype "bidirectional"))
      (node (ref "R26") (pin "2") (pinfunction "2_2") (pintype "passive"))
      (node (ref "RAM") (pin "F9") (pinfunction "ODT_F9") (pintype "bidirectional"))
    )
    (net (code "132") (name "M3RASN") (class "Default")
      (node (ref "FPGA") (pin "J6") (pinfunction "IO_L43P_GCLK23_M3RASN_3_J6") (pintype "bidirectional"))
      (node (ref "RAM") (pin "F7") (pinfunction "RAS#_F7") (pintype "bidirectional"))
    )
    (net (code "133") (name "M3WEN") (class "Default")
      (node (ref "FPGA") (pin "C1") (pinfunction "IO_L50P_M3WE_3_C1") (pintype "bidirectional"))
      (node (ref "RAM") (pin "F3") (pinfunction "WE#_F3") (pintype "bidirectional"))
    )
    (net (code "134") (name "MCO1_CLK") (class "Default")
      (node (ref "FPGA") (pin "J16") (pinfunction "IO_L43N_GCLK4_M1DQ5_1_J16") (pintype "bidirectional"))
      (node (ref "MCU") (pin "67") (pinfunction "MCO1_67") (pintype "bidirectional"))
    )
    (net (code "135") (name "Net-(A/V-L)") (class "Default")
      (node (ref "A/V") (pin "TIP") (pinfunction "L_TIP") (pintype "bidirectional"))
      (node (ref "C35") (pin "C") (pinfunction "-_C") (pintype "passive"))
    )
    (net (code "136") (name "Net-(A/V-R)") (class "Default")
      (node (ref "A/V") (pin "RING1") (pinfunction "R_RING1") (pintype "bidirectional"))
      (node (ref "C34") (pin "C") (pinfunction "-_C") (pintype "passive"))
    )
    (net (code "137") (name "Net-(A/V-VID)") (class "Default")
      (node (ref "A/V") (pin "SLEEVE") (pinfunction "VID_SLEEVE") (pintype "bidirectional"))
      (node (ref "C16") (pin "2") (pinfunction "2_2") (pintype "passive"))
      (node (ref "R51") (pin "2") (pinfunction "2_2") (pintype "passive"))
      (node (ref "R56") (pin "1") (pinfunction "1_1") (pintype "passive"))
    )
    (net (code "138") (name "Net-(ACTIVITY-PadA)") (class "Default")
      (node (ref "ACTIVITY") (pin "A") (pinfunction "A_A") (pintype "passive"))
      (node (ref "R3") (pin "2") (pinfunction "2_2") (pintype "passive"))
    )
    (net (code "139") (name "Net-(BAT-+)") (class "Default")
      (node (ref "BAT") (pin "PWR@1") (pinfunction "+_PWR@1") (pintype "power_in"))
      (node (ref "MCU") (pin "6") (pinfunction "VBAT_6") (pintype "bidirectional"))
    )
    (net (code "140") (name "Net-(BUSPWR-Pad1)") (class "Default")
      (node (ref "BUSPWR") (pin "1") (pinfunction "1_1") (pintype "passive"))
      (node (ref "FUSE") (pin "1") (pinfunction "1_1") (pintype "bidirectional"))
    )
    (net (code "141") (name "Net-(C34-+)") (class "Default")
      (node (ref "C15") (pin "2") (pinfunction "2_2") (pintype "passive"))
      (node (ref "C34") (pin "A") (pinfunction "+_A") (pintype "passive"))
      (node (ref "R50") (pin "2") (pinfunction "2_2") (pintype "passive"))
    )
    (net (code "142") (name "Net-(C35-+)") (class "Default")
      (node (ref "C14") (pin "2") (pinfunction "2_2") (pintype "passive"))
      (node (ref "C35") (pin "A") (pinfunction "+_A") (pintype "passive"))
      (node (ref "R16") (pin "2") (pinfunction "2_2") (pintype "passive"))
    )
    (net (code "143") (name "Net-(DEVICE-SH1)") (class "Default")
      (node (ref "C4") (pin "2") (pinfunction "2_2") (pintype "passive"))
      (node (ref "DEVICE") (pin "MNT1") (pinfunction "SH1_MNT1") (pintype "bidirectional"))
      (node (ref "DEVICE") (pin "MNT2") (pinfunction "SH2_MNT2") (pintype "bidirectional"))
      (node (ref "DEVICE") (pin "MNT3") (pinfunction "SH3_MNT3") (pintype "bidirectional"))
      (node (ref "DEVICE") (pin "MNT4") (pinfunction "SH4_MNT4") (pintype "bidirectional"))
    )
    (net (code "144") (name "Net-(FUSE-Pad2)") (class "Default")
      (node (ref "FUSE") (pin "2") (pinfunction "2_2") (pintype "bidirectional"))
      (node (ref "L1") (pin "1") (pinfunction "1_1") (pintype "passive"))
    )
    (net (code "145") (name "Net-(HOST-PadDM)") (class "Default")
      (node (ref "HOST") (pin "DM") (pinfunction "DM_DM") (pintype "bidirectional"))
      (node (ref "R40") (pin "2") (pinfunction "2_2") (pintype "passive"))
    )
    (net (code "146") (name "Net-(HOST-PadDP)") (class "Default")
      (node (ref "HOST") (pin "DP") (pinfunction "DP_DP") (pintype "bidirectional"))
      (node (ref "R39") (pin "2") (pinfunction "2_2") (pintype "passive"))
    )
    (net (code "147") (name "Net-(LVDS-+5V)") (class "Default")
      (node (ref "LVDS") (pin "P18") (pinfunction "+5V_P18") (pintype "bidirectional"))
      (node (ref "R19") (pin "1") (pinfunction "1_1") (pintype "passive"))
    )
    (net (code "148") (name "Net-(LVDS-DDC_CLK)") (class "Default")
      (node (ref "LVDS") (pin "P15") (pinfunction "DDC_CLK_P15") (pintype "bidirectional"))
      (node (ref "R17") (pin "1") (pinfunction "1_1") (pintype "passive"))
    )
    (net (code "149") (name "Net-(LVDS-DDC_DATA)") (class "Default")
      (node (ref "LVDS") (pin "P16") (pinfunction "DDC_DATA_P16") (pintype "bidirectional"))
      (node (ref "R18") (pin "1") (pinfunction "1_1") (pintype "passive"))
    )
    (net (code "150") (name "Net-(LVDS-DETECT)") (class "Default")
      (node (ref "LVDS") (pin "P19") (pinfunction "DETECT_P19") (pintype "bidirectional"))
      (node (ref "R13") (pin "2") (pinfunction "2_2") (pintype "passive"))
    )
    (net (code "151") (name "Net-(MCUB-OSC32_IN)") (class "Default")
      (node (ref "C59") (pin "2") (pinfunction "2_2") (pintype "passive"))
      (node (ref "MCU") (pin "8") (pinfunction "OSC32_IN_8") (pintype "bidirectional"))
      (node (ref "RTC") (pin "1") (pinfunction "1_1") (pintype "passive"))
    )
    (net (code "152") (name "Net-(MCUB-OSC32_OUT)") (class "Default")
      (node (ref "C58") (pin "2") (pinfunction "2_2") (pintype "passive"))
      (node (ref "MCU") (pin "9") (pinfunction "OSC32_OUT_9") (pintype "bidirectional"))
      (node (ref "RTC") (pin "4") (pinfunction "2_4") (pintype "passive"))
    )
    (net (code "153") (name "Net-(MCUF-VCAP_1)") (class "Default")
      (node (ref "C7") (pin "2") (pinfunction "2_2") (pintype "passive"))
      (node (ref "MCU") (pin "49") (pinfunction "VCAP_1_49") (pintype "bidirectional"))
    )
    (net (code "154") (name "Net-(MCUF-VCAP_2)") (class "Default")
      (node (ref "C8") (pin "1") (pinfunction "1_1") (pintype "passive"))
      (node (ref "MCU") (pin "73") (pinfunction "VCAP_2_73") (pintype "bidirectional"))
    )
    (net (code "155") (name "Net-(MCUG-SDIO_CLK)") (class "Default")
      (node (ref "MCU") (pin "80") (pinfunction "SDIO_CLK_80") (pintype "bidirectional"))
      (node (ref "WIFI/BT") (pin "17") (pinfunction "SD_CLK_17") (pintype "bidirectional"))
    )
    (net (code "156") (name "Net-(MCUG-SDIO_CMD)") (class "Default")
      (node (ref "MCU") (pin "83") (pinfunction "SDIO_CMD_83") (pintype "bidirectional"))
      (node (ref "R44") (pin "2") (pinfunction "2_2") (pintype "passive"))
      (node (ref "WIFI/BT") (pin "16") (pinfunction "SD_CMD_16") (pintype "bidirectional"))
    )
    (net (code "157") (name "Net-(MCUG-SDIO_D0)") (class "Default")
      (node (ref "MCU") (pin "65") (pinfunction "SDIO_D0_65") (pintype "bidirectional"))
      (node (ref "R10") (pin "2") (pinfunction "2_2") (pintype "passive"))
      (node (ref "WIFI/BT") (pin "18") (pinfunction "SD_D0_18") (pintype "bidirectional"))
    )
    (net (code "158") (name "Net-(MCUG-SDIO_D1)") (class "Default")
      (node (ref "MCU") (pin "66") (pinfunction "SDIO_D1_66") (pintype "bidirectional"))
      (node (ref "R41") (pin "2") (pinfunction "2_2") (pintype "passive"))
      (node (ref "WIFI/BT") (pin "19") (pinfunction "SD_D1_19") (pintype "bidirectional"))
    )
    (net (code "159") (name "Net-(MCUG-SDIO_D2)") (class "Default")
      (node (ref "MCU") (pin "78") (pinfunction "SDIO_D2_78") (pintype "bidirectional"))
      (node (ref "R42") (pin "2") (pinfunction "2_2") (pintype "passive"))
      (node (ref "WIFI/BT") (pin "14") (pinfunction "SD_D2_14") (pintype "bidirectional"))
    )
    (net (code "160") (name "Net-(MCUG-SDIO_D3)") (class "Default")
      (node (ref "MCU") (pin "79") (pinfunction "SDIO_D3_79") (pintype "bidirectional"))
      (node (ref "R43") (pin "2") (pinfunction "2_2") (pintype "passive"))
      (node (ref "WIFI/BT") (pin "15") (pinfunction "SD_D3_15") (pintype "bidirectional"))
    )
    (net (code "161") (name "Net-(MCUG-SDIO_EN)") (class "Default")
      (node (ref "MCU") (pin "7") (pinfunction "SDIO_EN_7") (pintype "bidirectional"))
      (node (ref "WIFI/BT") (pin "12") (pinfunction "WL_DIS#_12") (pintype "bidirectional"))
    )
    (net (code "162") (name "Net-(MCUJ-USB_FS_DM)") (class "Default")
      (node (ref "MCU") (pin "70") (pinfunction "USB_FS_DM_70") (pintype "bidirectional"))
      (node (ref "R38") (pin "2") (pinfunction "2_2") (pintype "passive"))
    )
    (net (code "163") (name "Net-(MCUJ-USB_FS_DP)") (class "Default")
      (node (ref "MCU") (pin "71") (pinfunction "USB_FS_DP_71") (pintype "bidirectional"))
      (node (ref "R37") (pin "2") (pinfunction "2_2") (pintype "passive"))
    )
    (net (code "164") (name "Net-(MCUJ-USB_HS_DM)") (class "Default")
      (node (ref "MCU") (pin "53") (pinfunction "USB_HS_DM_53") (pintype "bidirectional"))
      (node (ref "R40") (pin "1") (pinfunction "1_1") (pintype "passive"))
    )
    (net (code "165") (name "Net-(MCUJ-USB_HS_DP)") (class "Default")
      (node (ref "MCU") (pin "54") (pinfunction "USB_HS_DP_54") (pintype "bidirectional"))
      (node (ref "R39") (pin "1") (pinfunction "1_1") (pintype "passive"))
    )
    (net (code "166") (name "Net-(MICROSD-VDD)") (class "Default")
      (node (ref "C12") (pin "2") (pinfunction "2_2") (pintype "passive"))
      (node (ref "MICROSD") (pin "P4") (pinfunction "VDD_P4") (pintype "bidirectional"))
      (node (ref "R34") (pin "2") (pinfunction "2_2") (pintype "passive"))
    )
    (net (code "167") (name "Net-(PIXEL-DOUT)") (class "Default")
      (node (ref "CASCADE") (pin "2") (pinfunction "2_2") (pintype "passive"))
      (node (ref "PIXEL") (pin "2-DOUT") (pinfunction "DOUT_2-DOUT") (pintype "output"))
    )
    (net (code "168") (name "Net-(R52-Pad2)") (class "Default")
      (node (ref "R52") (pin "2") (pinfunction "2_2") (pintype "passive"))
      (node (ref "R56") (pin "2") (pinfunction "2_2") (pintype "passive"))
      (node (ref "R57") (pin "1") (pinfunction "1_1") (pintype "passive"))
    )
    (net (code "169") (name "Net-(R53-Pad2)") (class "Default")
      (node (ref "R53") (pin "2") (pinfunction "2_2") (pintype "passive"))
      (node (ref "R57") (pin "2") (pinfunction "2_2") (pintype "passive"))
      (node (ref "R58") (pin "1") (pinfunction "1_1") (pintype "passive"))
    )
    (net (code "170") (name "Net-(R54-Pad2)") (class "Default")
      (node (ref "R54") (pin "2") (pinfunction "2_2") (pintype "passive"))
      (node (ref "R58") (pin "2") (pinfunction "2_2") (pintype "passive"))
      (node (ref "R59") (pin "1") (pinfunction "1_1") (pintype "passive"))
    )
    (net (code "171") (name "Net-(R55-Pad2)") (class "Default")
      (node (ref "R55") (pin "2") (pinfunction "2_2") (pintype "passive"))
      (node (ref "R59") (pin "2") (pinfunction "2_2") (pintype "passive"))
      (node (ref "R60") (pin "2") (pinfunction "2_2") (pintype "passive"))
    )
    (net (code "172") (name "Net-(VREG12-FB)") (class "Default")
      (node (ref "C51") (pin "1") (pinfunction "1_1") (pintype "passive"))
      (node (ref "R66") (pin "2") (pinfunction "2_2") (pintype "passive"))
      (node (ref "R67") (pin "2") (pinfunction "2_2") (pintype "passive"))
      (node (ref "VREG12") (pin "5") (pinfunction "FB_5") (pintype "bidirectional"))
    )
    (net (code "173") (name "Net-(VREG12-LX)") (class "Default")
      (node (ref "L4") (pin "2") (pinfunction "2_2") (pintype "passive"))
      (node (ref "VREG12") (pin "3") (pinfunction "LX_3") (pintype "bidirectional"))
    )
    (net (code "174") (name "Net-(VREG18-FB)") (class "Default")
      (node (ref "C22") (pin "2") (pinfunction "2_2") (pintype "passive"))
      (node (ref "R64") (pin "1") (pinfunction "1_1") (pintype "passive"))
      (node (ref "R65") (pin "1") (pinfunction "1_1") (pintype "passive"))
      (node (ref "VREG18") (pin "5") (pinfunction "FB_5") (pintype "bidirectional"))
    )
    (net (code "175") (name "Net-(VREG18-LX)") (class "Default")
      (node (ref "L5") (pin "1") (pinfunction "1_1") (pintype "passive"))
      (node (ref "VREG18") (pin "3") (pinfunction "LX_3") (pintype "bidirectional"))
    )
    (net (code "176") (name "Net-(VREG33-FB)") (class "Default")
      (node (ref "C21") (pin "1") (pinfunction "1_1") (pintype "passive"))
      (node (ref "R49") (pin "1") (pinfunction "1_1") (pintype "passive"))
      (node (ref "R63") (pin "2") (pinfunction "2_2") (pintype "passive"))
      (node (ref "VREG33") (pin "5") (pinfunction "FB_5") (pintype "bidirectional"))
    )
    (net (code "177") (name "Net-(VREG33-LX)") (class "Default")
      (node (ref "L6") (pin "1") (pinfunction "1_1") (pintype "passive"))
      (node (ref "VREG33") (pin "3") (pinfunction "LX_3") (pintype "bidirectional"))
    )
    (net (code "178") (name "Net-(WIFI/BT-WIFI{slash}BT_ANT)") (class "Default")
      (node (ref "ANTENNA") (pin "FEED") (pinfunction "FEED_FEED") (pintype "bidirectional"))
      (node (ref "WIFI/BT") (pin "2") (pinfunction "WIFI/BT_ANT_2") (pintype "bidirectional"))
    )
    (net (code "179") (name "PIXEL_DOUT") (class "Default")
      (node (ref "MCU") (pin "95") (pinfunction "PB8_95") (pintype "bidirectional"))
      (node (ref "PIXEL") (pin "4-DIN") (pinfunction "DIN_4-DIN") (pintype "input"))
      (node (ref "R2") (pin "1") (pinfunction "1_1") (pintype "passive"))
    )
    (net (code "180") (name "SD_CLK") (class "Default")
      (node (ref "MCU") (pin "30") (pinfunction "SPI1_SCK_30") (pintype "bidirectional"))
      (node (ref "MICROSD") (pin "P5") (pinfunction "SCLK_P5") (pintype "bidirectional"))
      (node (ref "R14") (pin "2") (pinfunction "2_2") (pintype "passive"))
    )
    (net (code "181") (name "SD_CS") (class "Default")
      (node (ref "MCU") (pin "29") (pinfunction "SPI1_NSS_29") (pintype "bidirectional"))
      (node (ref "MICROSD") (pin "P2") (pinfunction "CS_P2") (pintype "bidirectional"))
      (node (ref "R22") (pin "2") (pinfunction "2_2") (pintype "passive"))
    )
    (net (code "182") (name "SD_DETECT") (class "Default")
      (node (ref "MCU") (pin "33") (pinfunction "PC4_33") (pintype "bidirectional"))
      (node (ref "MICROSD") (pin "P9") (pinfunction "DETECT_P9") (pintype "bidirectional"))
      (node (ref "R33") (pin "1") (pinfunction "1_1") (pintype "passive"))
    )
    (net (code "183") (name "SD_DI") (class "Default")
      (node (ref "MCU") (pin "32") (pinfunction "SPI1_MOSI_32") (pintype "bidirectional"))
      (node (ref "MICROSD") (pin "P3") (pinfunction "DI_P3") (pintype "bidirectional"))
      (node (ref "R31") (pin "2") (pinfunction "2_2") (pintype "passive"))
    )
    (net (code "184") (name "SD_DO") (class "Default")
      (node (ref "MCU") (pin "31") (pinfunction "SPI1_MISO_31") (pintype "bidirectional"))
      (node (ref "MICROSD") (pin "P7") (pinfunction "DO_P7") (pintype "bidirectional"))
      (node (ref "R32") (pin "1") (pinfunction "1_1") (pintype "passive"))
    )
    (net (code "185") (name "TMDS_CLKN") (class "Default")
      (node (ref "FPGA") (pin "T4") (pinfunction "IO_L63N_2_T4") (pintype "bidirectional"))
      (node (ref "LVDS") (pin "P12") (pinfunction "TMDS_CLKN_P12") (pintype "bidirectional"))
    )
    (net (code "186") (name "TMDS_CLKP") (class "Default")
      (node (ref "FPGA") (pin "P4") (pinfunction "IO_L63P_2_P4") (pintype "bidirectional"))
      (node (ref "LVDS") (pin "P10") (pinfunction "TMDS_CLKP_P10") (pintype "bidirectional"))
    )
    (net (code "187") (name "TMDS_D0N") (class "Default")
      (node (ref "FPGA") (pin "T5") (pinfunction "IO_L48N_RDWR_B_VREF_2_T5") (pintype "bidirectional"))
      (node (ref "LVDS") (pin "P9") (pinfunction "TMDS_D0N_P9") (pintype "bidirectional"))
    )
    (net (code "188") (name "TMDS_D0P") (class "Default")
      (node (ref "FPGA") (pin "R5") (pinfunction "IO_L48P_D7_2_R5") (pintype "bidirectional"))
      (node (ref "LVDS") (pin "P7") (pinfunction "TMDS_D0P_P7") (pintype "bidirectional"))
    )
    (net (code "189") (name "TMDS_D1N") (class "Default")
      (node (ref "FPGA") (pin "T7") (pinfunction "IO_L32N_GCLK28_2_T7") (pintype "bidirectional"))
      (node (ref "LVDS") (pin "P6") (pinfunction "TMDS_D1N_P6") (pintype "bidirectional"))
    )
    (net (code "190") (name "TMDS_D1P") (class "Default")
      (node (ref "FPGA") (pin "R7") (pinfunction "IO_L32P_GCLK29_2_R7") (pintype "bidirectional"))
      (node (ref "LVDS") (pin "P4") (pinfunction "TMDS_D1P_P4") (pintype "bidirectional"))
    )
    (net (code "191") (name "TMDS_D2N") (class "Default")
      (node (ref "FPGA") (pin "T9") (pinfunction "IO_L23N_2_T9") (pintype "bidirectional"))
      (node (ref "LVDS") (pin "P3") (pinfunction "TMDS_D2N_P3") (pintype "bidirectional"))
    )
    (net (code "192") (name "TMDS_D2P") (class "Default")
      (node (ref "FPGA") (pin "R9") (pinfunction "IO_L23P_2_R9") (pintype "bidirectional"))
      (node (ref "LVDS") (pin "P1") (pinfunction "TMDS_D2P_P1") (pintype "bidirectional"))
    )
    (net (code "193") (name "USB_DEVICE_DM") (class "Default")
      (node (ref "DEVICE") (pin "2") (pinfunction "D-_2") (pintype "bidirectional"))
      (node (ref "R38") (pin "1") (pinfunction "1_1") (pintype "passive"))
    )
    (net (code "194") (name "USB_DEVICE_DP") (class "Default")
      (node (ref "DEVICE") (pin "3") (pinfunction "D+_3") (pintype "bidirectional"))
      (node (ref "R37") (pin "1") (pinfunction "1_1") (pintype "passive"))
    )
    (net (code "195") (name "USB_DEVICE_VBUS") (class "Default")
      (node (ref "BUSPWR") (pin "2") (pinfunction "2_2") (pintype "passive"))
      (node (ref "DEVICE") (pin "1") (pinfunction "VBUS_1") (pintype "bidirectional"))
      (node (ref "MCU") (pin "68") (pinfunction "USB_FS_VBUS_68") (pintype "bidirectional"))
    )
    (net (code "196") (name "USB_FLG") (class "Default")
      (node (ref "MCU") (pin "96") (pinfunction "PB9_96") (pintype "bidirectional"))
      (node (ref "PWRSW") (pin "3") (pinfunction "FLG_3") (pintype "bidirectional"))
    )
    (net (code "197") (name "USER_BTN") (class "Default")
      (node (ref "MCU") (pin "48") (pinfunction "PB11_48") (pintype "bidirectional"))
      (node (ref "R27") (pin "1") (pinfunction "1_1") (pintype "passive"))
      (node (ref "USER") (pin "1") (pinfunction "A_1") (pintype "bidirectional"))
    )
    (net (code "198") (name "VIDEO_D0") (class "Default")
      (node (ref "FPGA") (pin "P12") (pinfunction "IO_L12N_D2_MISO3_2_P12") (pintype "bidirectional"))
      (node (ref "R55") (pin "1") (pinfunction "1_1") (pintype "passive"))
    )
    (net (code "199") (name "VIDEO_D1") (class "Default")
      (node (ref "FPGA") (pin "N9") (pinfunction "IO_L14P_D11_2_N9") (pintype "bidirectional"))
      (node (ref "R54") (pin "1") (pinfunction "1_1") (pintype "passive"))
    )
    (net (code "200") (name "VIDEO_D2") (class "Default")
      (node (ref "FPGA") (pin "P11") (pinfunction "IO_L13N_D10_2_P11") (pintype "bidirectional"))
      (node (ref "R53") (pin "1") (pinfunction "1_1") (pintype "passive"))
    )
    (net (code "201") (name "VIDEO_D3") (class "Default")
      (node (ref "FPGA") (pin "P9") (pinfunction "IO_L14N_D12_2_P9") (pintype "bidirectional"))
      (node (ref "R52") (pin "1") (pinfunction "1_1") (pintype "passive"))
    )
    (net (code "202") (name "VIDEO_D4") (class "Default")
      (node (ref "FPGA") (pin "T10") (pinfunction "IO_L3N_MOSI_CSI_B_MISO0_2_T10") (pintype "bidirectional"))
      (node (ref "R51") (pin "1") (pinfunction "1_1") (pintype "passive"))
    )
    (net (code "203") (name "WIFI_INT") (class "Default")
      (node (ref "MCU") (pin "91") (pinfunction "PB5_91") (pintype "bidirectional"))
    )
    (net (code "204") (name "unconnected-(A/V-SW-PadTIP-SWITCH)") (class "Default")
      (node (ref "A/V") (pin "TIP-SWITCH") (pinfunction "SW_TIP-SWITCH") (pintype "bidirectional"))
    )
    (net (code "205") (name "unconnected-(FPGAA-IO_L5N_0-PadE6)") (class "Default")
      (node (ref "FPGA") (pin "E6") (pinfunction "IO_L5N_0_E6") (pintype "bidirectional"))
    )
    (net (code "206") (name "unconnected-(FPGAA-IO_L5P_0-PadF7)") (class "Default")
      (node (ref "FPGA") (pin "F7") (pinfunction "IO_L5P_0_F7") (pintype "bidirectional"))
    )
    (net (code "207") (name "unconnected-(FPGAA-IO_L35P_GCLK17_0-PadB10)") (class "Default")
      (node (ref "FPGA") (pin "B10") (pinfunction "IO_L35P_GCLK17_0_B10") (pintype "bidirectional"))
    )
    (net (code "208") (name "unconnected-(FPGAA-IO_L36N_GCLK14_0-PadE8)") (class "Default")
      (node (ref "FPGA") (pin "E8") (pinfunction "IO_L36N_GCLK14_0_E8") (pintype "bidirectional"))
    )
    (net (code "209") (name "unconnected-(FPGAA-IO_L36P_GCLK15_0-PadE7)") (class "Default")
      (node (ref "FPGA") (pin "E7") (pinfunction "IO_L36P_GCLK15_0_E7") (pintype "bidirectional"))
    )
    (net (code "210") (name "unconnected-(FPGAA-IO_L37P_GCLK13_0-PadE10)") (class "Default")
      (node (ref "FPGA") (pin "E10") (pinfunction "IO_L37P_GCLK13_0_E10") (pintype "bidirectional"))
    )
    (net (code "211") (name "unconnected-(FPGAA-IO_L40P_0-PadF9)") (class "Default")
      (node (ref "FPGA") (pin "F9") (pinfunction "IO_L40P_0_F9") (pintype "bidirectional"))
    )
    (net (code "212") (name "unconnected-(FPGAA-IO_L64N_SCP4_0-PadE11)") (class "Default")
      (node (ref "FPGA") (pin "E11") (pinfunction "IO_L64N_SCP4_0_E11") (pintype "bidirectional"))
    )
    (net (code "213") (name "unconnected-(FPGAA-IO_L64P_SCP5_0-PadF10)") (class "Default")
      (node (ref "FPGA") (pin "F10") (pinfunction "IO_L64P_SCP5_0_F10") (pintype "bidirectional"))
    )
    (net (code "214") (name "unconnected-(FPGAA-IO_L66P_SCP1_0-PadD11)") (class "Default")
      (node (ref "FPGA") (pin "D11") (pinfunction "IO_L66P_SCP1_0_D11") (pintype "bidirectional"))
    )
    (net (code "215") (name "unconnected-(FPGAB-IO_L1N_A24_VREF_1-PadE12)") (class "Default")
      (node (ref "FPGA") (pin "E12") (pinfunction "IO_L1N_A24_VREF_1_E12") (pintype "bidirectional"))
    )
    (net (code "216") (name "unconnected-(FPGAB-IO_L1P_A25_1-PadE13)") (class "Default")
      (node (ref "FPGA") (pin "E13") (pinfunction "IO_L1P_A25_1_E13") (pintype "bidirectional"))
    )
    (net (code "217") (name "unconnected-(FPGAB-IO_L30N_A20_M1A11_1-PadG11)") (class "Default")
      (node (ref "FPGA") (pin "G11") (pinfunction "IO_L30N_A20_M1A11_1_G11") (pintype "bidirectional"))
    )
    (net (code "218") (name "unconnected-(FPGAB-IO_L30P_A21_M1RESET_1-PadF12)") (class "Default")
      (node (ref "FPGA") (pin "F12") (pinfunction "IO_L30P_A21_M1RESET_1_F12") (pintype "bidirectional"))
    )
    (net (code "219") (name "unconnected-(FPGAB-IO_L32P_A17_M1A8_1-PadF13)") (class "Default")
      (node (ref "FPGA") (pin "F13") (pinfunction "IO_L32P_A17_M1A8_1_F13") (pintype "bidirectional"))
    )
    (net (code "220") (name "unconnected-(FPGAB-IO_L38N_A4_M1CLKN_1-PadH11)") (class "Default")
      (node (ref "FPGA") (pin "H11") (pinfunction "IO_L38N_A4_M1CLKN_1_H11") (pintype "bidirectional"))
    )
    (net (code "221") (name "unconnected-(FPGAB-IO_L38P_A5_M1CLK_1-PadG12)") (class "Default")
      (node (ref "FPGA") (pin "G12") (pinfunction "IO_L38P_A5_M1CLK_1_G12") (pintype "bidirectional"))
    )
    (net (code "222") (name "unconnected-(FPGAB-IO_L40N_GCLK10_M1A6_1-PadJ12)") (class "Default")
      (node (ref "FPGA") (pin "J12") (pinfunction "IO_L40N_GCLK10_M1A6_1_J12") (pintype "bidirectional"))
    )
    (net (code "223") (name "unconnected-(FPGAB-IO_L40P_GCLK11_M1A5_1-PadJ11)") (class "Default")
      (node (ref "FPGA") (pin "J11") (pinfunction "IO_L40P_GCLK11_M1A5_1_J11") (pintype "bidirectional"))
    )
    (net (code "224") (name "unconnected-(FPGAB-IO_L41P_GCLK9_IRDY1_M1RASN_1-PadJ13)") (class "Default")
      (node (ref "FPGA") (pin "J13") (pinfunction "IO_L41P_GCLK9_IRDY1_M1RASN_1_J13") (pintype "bidirectional"))
    )
    (net (code "225") (name "unconnected-(FPGAB-IO_L42N_GCLK6_TRDY1_M1LDM_1-PadK11)") (class "Default")
      (node (ref "FPGA") (pin "K11") (pinfunction "IO_L42N_GCLK6_TRDY1_M1LDM_1_K11") (pintype "bidirectional"))
    )
    (net (code "226") (name "unconnected-(FPGAB-IO_L42P_GCLK7_M1UDM_1-PadK12)") (class "Default")
      (node (ref "FPGA") (pin "K12") (pinfunction "IO_L42P_GCLK7_M1UDM_1_K12") (pintype "bidirectional"))
    )
    (net (code "227") (name "unconnected-(FPGAB-IO_L43P_GCLK5_M1DQ4_1-PadJ14)") (class "Default")
      (node (ref "FPGA") (pin "J14") (pinfunction "IO_L43P_GCLK5_M1DQ4_1_J14") (pintype "bidirectional"))
    )
    (net (code "228") (name "unconnected-(FPGAB-IO_L51N_M1DQ13_1-PadT13)") (class "Default")
      (node (ref "FPGA") (pin "T13") (pinfunction "IO_L51N_M1DQ13_1_T13") (pintype "bidirectional"))
    )
    (net (code "229") (name "unconnected-(FPGAB-IO_L52N_M1DQ15_1-PadT12)") (class "Default")
      (node (ref "FPGA") (pin "T12") (pinfunction "IO_L52N_M1DQ15_1_T12") (pintype "bidirectional"))
    )
    (net (code "230") (name "unconnected-(FPGAB-IO_L52P_M1DQ14_1-PadR12)") (class "Default")
      (node (ref "FPGA") (pin "R12") (pinfunction "IO_L52P_M1DQ14_1_R12") (pintype "bidirectional"))
    )
    (net (code "231") (name "unconnected-(FPGAB-IO_L53N_VREF_1-PadL13)") (class "Default")
      (node (ref "FPGA") (pin "L13") (pinfunction "IO_L53N_VREF_1_L13") (pintype "bidirectional"))
    )
    (net (code "232") (name "unconnected-(FPGAB-IO_L53P_1-PadL12)") (class "Default")
      (node (ref "FPGA") (pin "L12") (pinfunction "IO_L53P_1_L12") (pintype "bidirectional"))
    )
    (net (code "233") (name "unconnected-(FPGAB-IO_L74P_AWAKE_1-PadM13)") (class "Default")
      (node (ref "FPGA") (pin "M13") (pinfunction "IO_L74P_AWAKE_1_M13") (pintype "bidirectional"))
    )
    (net (code "234") (name "unconnected-(FPGAC-CMPCS_B_2-PadL11)") (class "Default")
      (node (ref "FPGA") (pin "L11") (pinfunction "CMPCS_B_2_L11") (pintype "bidirectional"))
    )
    (net (code "235") (name "unconnected-(FPGAC-IO_L2N_CMPMOSI_2-PadM11)") (class "Default")
      (node (ref "FPGA") (pin "M11") (pinfunction "IO_L2N_CMPMOSI_2_M11") (pintype "bidirectional"))
    )
    (net (code "236") (name "unconnected-(FPGAC-IO_L16N_VREF_2-PadM10)") (class "Default")
      (node (ref "FPGA") (pin "M10") (pinfunction "IO_L16N_VREF_2_M10") (pintype "bidirectional"))
    )
    (net (code "237") (name "unconnected-(FPGAC-IO_L16P_2-PadL10)") (class "Default")
      (node (ref "FPGA") (pin "L10") (pinfunction "IO_L16P_2_L10") (pintype "bidirectional"))
    )
    (net (code "238") (name "unconnected-(FPGAC-IO_L29N_GCLK2_2-PadN8)") (class "Default")
      (node (ref "FPGA") (pin "N8") (pinfunction "IO_L29N_GCLK2_2_N8") (pintype "bidirectional"))
    )
    (net (code "239") (name "unconnected-(FPGAC-IO_L29P_GCLK3_2-PadM9)") (class "Default")
      (node (ref "FPGA") (pin "M9") (pinfunction "IO_L29P_GCLK3_2_M9") (pintype "bidirectional"))
    )
    (net (code "240") (name "unconnected-(FPGAC-IO_L30N_GCLK0_USERCCLK_2-PadT8)") (class "Default")
      (node (ref "FPGA") (pin "T8") (pinfunction "IO_L30N_GCLK0_USERCCLK_2_T8") (pintype "bidirectional"))
    )
    (net (code "241") (name "unconnected-(FPGAC-IO_L30P_GCLK1_D13_2-PadP8)") (class "Default")
      (node (ref "FPGA") (pin "P8") (pinfunction "IO_L30P_GCLK1_D13_2_P8") (pintype "bidirectional"))
    )
    (net (code "242") (name "unconnected-(FPGAC-IO_L31N_GCLK30_D15_2-PadM7)") (class "Default")
      (node (ref "FPGA") (pin "M7") (pinfunction "IO_L31N_GCLK30_D15_2_M7") (pintype "bidirectional"))
    )
    (net (code "243") (name "unconnected-(FPGAC-IO_L31P_GCLK31_D14_2-PadP7)") (class "Default")
      (node (ref "FPGA") (pin "P7") (pinfunction "IO_L31P_GCLK31_D14_2_P7") (pintype "bidirectional"))
    )
    (net (code "244") (name "unconnected-(FPGAC-IO_L47N_2-PadT6)") (class "Default")
      (node (ref "FPGA") (pin "T6") (pinfunction "IO_L47N_2_T6") (pintype "bidirectional"))
    )
    (net (code "245") (name "unconnected-(FPGAC-IO_L47P_2-PadP6)") (class "Default")
      (node (ref "FPGA") (pin "P6") (pinfunction "IO_L47P_2_P6") (pintype "bidirectional"))
    )
    (net (code "246") (name "unconnected-(FPGAC-IO_L49N_D4_2-PadP5)") (class "Default")
      (node (ref "FPGA") (pin "P5") (pinfunction "IO_L49N_D4_2_P5") (pintype "bidirectional"))
    )
    (net (code "247") (name "unconnected-(FPGAC-IO_L49P_D3_2-PadN5)") (class "Default")
      (node (ref "FPGA") (pin "N5") (pinfunction "IO_L49P_D3_2_N5") (pintype "bidirectional"))
    )
    (net (code "248") (name "unconnected-(FPGAC-IO_L62N_D6_2-PadL7)") (class "Default")
      (node (ref "FPGA") (pin "L7") (pinfunction "IO_L62N_D6_2_L7") (pintype "bidirectional"))
    )
    (net (code "249") (name "unconnected-(FPGAC-IO_L62P_D5_2-PadL8)") (class "Default")
      (node (ref "FPGA") (pin "L8") (pinfunction "IO_L62P_D5_2_L8") (pintype "bidirectional"))
    )
    (net (code "250") (name "unconnected-(FPGAC-IO_L64N_D9_2-PadN6)") (class "Default")
      (node (ref "FPGA") (pin "N6") (pinfunction "IO_L64N_D9_2_N6") (pintype "bidirectional"))
    )
    (net (code "251") (name "unconnected-(FPGAC-IO_L64P_D8_2-PadM6)") (class "Default")
      (node (ref "FPGA") (pin "M6") (pinfunction "IO_L64P_D8_2_M6") (pintype "bidirectional"))
    )
    (net (code "252") (name "unconnected-(FPGAC-IO_L65N_CSO_B_2-PadT3)") (class "Default")
      (node (ref "FPGA") (pin "T3") (pinfunction "IO_L65N_CSO_B_2_T3") (pintype "bidirectional"))
    )
    (net (code "253") (name "unconnected-(FPGAD-IO_L2N_3-PadN4)") (class "Default")
      (node (ref "FPGA") (pin "N4") (pinfunction "IO_L2N_3_N4") (pintype "bidirectional"))
    )
    (net (code "254") (name "unconnected-(FPGAD-IO_L2P_3-PadM5)") (class "Default")
      (node (ref "FPGA") (pin "M5") (pinfunction "IO_L2P_3_M5") (pintype "bidirectional"))
    )
    (net (code "255") (name "unconnected-(FPGAD-IO_L32N_M3DQ15_3-PadR1)") (class "Default")
      (node (ref "FPGA") (pin "R1") (pinfunction "IO_L32N_M3DQ15_3_R1") (pintype "bidirectional"))
    )
    (net (code "256") (name "unconnected-(FPGAD-IO_L32P_M3DQ14_3-PadR2)") (class "Default")
      (node (ref "FPGA") (pin "R2") (pinfunction "IO_L32P_M3DQ14_3_R2") (pintype "bidirectional"))
    )
    (net (code "257") (name "unconnected-(FPGAD-IO_L33N_M3DQ13_3-PadP1)") (class "Default")
      (node (ref "FPGA") (pin "P1") (pinfunction "IO_L33N_M3DQ13_3_P1") (pintype "bidirectional"))
    )
    (net (code "258") (name "unconnected-(FPGAD-IO_L33P_M3DQ12_3-PadP2)") (class "Default")
      (node (ref "FPGA") (pin "P2") (pinfunction "IO_L33P_M3DQ12_3_P2") (pintype "bidirectional"))
    )
    (net (code "259") (name "unconnected-(FPGAD-IO_L34N_M3UDQSN_3-PadN1)") (class "Default")
      (node (ref "FPGA") (pin "N1") (pinfunction "IO_L34N_M3UDQSN_3_N1") (pintype "bidirectional"))
    )
    (net (code "260") (name "unconnected-(FPGAD-IO_L34P_M3UDQS_3-PadN3)") (class "Default")
      (node (ref "FPGA") (pin "N3") (pinfunction "IO_L34P_M3UDQS_3_N3") (pintype "bidirectional"))
    )
    (net (code "261") (name "unconnected-(FPGAD-IO_L35N_M3DQ11_3-PadM1)") (class "Default")
      (node (ref "FPGA") (pin "M1") (pinfunction "IO_L35N_M3DQ11_3_M1") (pintype "bidirectional"))
    )
    (net (code "262") (name "unconnected-(FPGAD-IO_L35P_M3DQ10_3-PadM2)") (class "Default")
      (node (ref "FPGA") (pin "M2") (pinfunction "IO_L35P_M3DQ10_3_M2") (pintype "bidirectional"))
    )
    (net (code "263") (name "unconnected-(FPGAD-IO_L36N_M3DQ9_3-PadL1)") (class "Default")
      (node (ref "FPGA") (pin "L1") (pinfunction "IO_L36N_M3DQ9_3_L1") (pintype "bidirectional"))
    )
    (net (code "264") (name "unconnected-(FPGAD-IO_L36P_M3DQ8_3-PadL3)") (class "Default")
      (node (ref "FPGA") (pin "L3") (pinfunction "IO_L36P_M3DQ8_3_L3") (pintype "bidirectional"))
    )
    (net (code "265") (name "unconnected-(FPGAD-IO_L42P_GCLK25_TRDY2_M3UDM_3-PadK3)") (class "Default")
      (node (ref "FPGA") (pin "K3") (pinfunction "IO_L42P_GCLK25_TRDY2_M3UDM_3_K3") (pintype "bidirectional"))
    )
    (net (code "266") (name "unconnected-(FPGAD-IO_L54P_M3RESET_3-PadE4)") (class "Default")
      (node (ref "FPGA") (pin "E4") (pinfunction "IO_L54P_M3RESET_3_E4") (pintype "bidirectional"))
    )
    (net (code "267") (name "unconnected-(FPGAD-IO_L83P_3-PadB3)") (class "Default")
      (node (ref "FPGA") (pin "B3") (pinfunction "IO_L83P_3_B3") (pintype "bidirectional"))
    )
    (net (code "268") (name "unconnected-(JTAG-FPGA-HALT-PadP14)") (class "Default")
      (node (ref "JTAG-FPGA") (pin "P14") (pinfunction "HALT_P14") (pintype "bidirectional"))
    )
    (net (code "269") (name "unconnected-(JTAG-FPGA-NC-PadP1)") (class "Default")
      (node (ref "JTAG-FPGA") (pin "P1") (pinfunction "NC_P1") (pintype "bidirectional"))
    )
    (net (code "270") (name "unconnected-(JTAG-FPGA-NC-PadP12)") (class "Default")
      (node (ref "JTAG-FPGA") (pin "P12") (pinfunction "NC_P12") (pintype "bidirectional"))
    )
    (net (code "271") (name "unconnected-(JTAG-FPGA-PGND-PadP13)") (class "Default")
      (node (ref "JTAG-FPGA") (pin "P13") (pinfunction "PGND_P13") (pintype "bidirectional"))
    )
    (net (code "272") (name "unconnected-(JTAG-MCU-GNDDET-PadP11)") (class "Default")
      (node (ref "JTAG-MCU") (pin "P11") (pinfunction "GNDDET_P11") (pintype "bidirectional"))
    )
    (net (code "273") (name "unconnected-(JTAG-MCU-NC-PadP1)") (class "Default")
      (node (ref "JTAG-MCU") (pin "P1") (pinfunction "NC_P1") (pintype "bidirectional"))
    )
    (net (code "274") (name "unconnected-(JTAG-MCU-NC-PadP2)") (class "Default")
      (node (ref "JTAG-MCU") (pin "P2") (pinfunction "NC_P2") (pintype "bidirectional"))
    )
    (net (code "275") (name "unconnected-(JTAG-MCU-T_JRCLK-PadP9)") (class "Default")
      (node (ref "JTAG-MCU") (pin "P9") (pinfunction "T_JRCLK_P9") (pintype "bidirectional"))
    )
    (net (code "276") (name "unconnected-(LVDS-CEC-PadP13)") (class "Default")
      (node (ref "LVDS") (pin "P13") (pinfunction "CEC_P13") (pintype "bidirectional"))
    )
    (net (code "277") (name "unconnected-(LVDS-RES-PadP14)") (class "Default")
      (node (ref "LVDS") (pin "P14") (pinfunction "RES_P14") (pintype "bidirectional"))
    )
    (net (code "278") (name "unconnected-(MCUB-OSC_OUT-Pad13)") (class "Default")
      (node (ref "MCU") (pin "13") (pinfunction "OSC_OUT_13") (pintype "bidirectional"))
    )
    (net (code "279") (name "unconnected-(MCUE-TRST-Pad90)") (class "Default")
      (node (ref "MCU") (pin "90") (pinfunction "TRST_90") (pintype "bidirectional"))
    )
    (net (code "280") (name "unconnected-(MICROSD-NC-PadNC1)") (class "Default")
      (node (ref "MICROSD") (pin "NC1") (pinfunction "NC_NC1") (pintype "bidirectional"))
    )
    (net (code "281") (name "unconnected-(MICROSD-NC-PadNC2)") (class "Default")
      (node (ref "MICROSD") (pin "NC2") (pinfunction "NC_NC2") (pintype "bidirectional"))
    )
    (net (code "282") (name "unconnected-(MICROSD-NC-PadP1)") (class "Default")
      (node (ref "MICROSD") (pin "P1") (pinfunction "NC_P1") (pintype "bidirectional"))
    )
    (net (code "283") (name "unconnected-(MICROSD-NC-PadP8)") (class "Default")
      (node (ref "MICROSD") (pin "P8") (pinfunction "NC_P8") (pintype "bidirectional"))
    )
    (net (code "284") (name "unconnected-(OSC10M-EN-Pad1)") (class "Default")
      (node (ref "OSC10M") (pin "1") (pinfunction "EN_1") (pintype "bidirectional"))
    )
    (net (code "285") (name "unconnected-(RAM-RDQS#-PadA2)") (class "Default")
      (node (ref "RAM") (pin "A2") (pinfunction "RDQS#_A2") (pintype "bidirectional"))
    )
    (net (code "286") (name "unconnected-(RAM-RFU{slash}A15-PadL7)") (class "Default")
      (node (ref "RAM") (pin "L7") (pinfunction "RFU/A15_L7") (pintype "bidirectional"))
    )
    (net (code "287") (name "unconnected-(WIFI/BT-BT_HOST_WAKE-Pad7)") (class "Default")
      (node (ref "WIFI/BT") (pin "7") (pinfunction "BT_HOST_WAKE_7") (pintype "bidirectional"))
    )
    (net (code "288") (name "unconnected-(WIFI/BT-WL_HOST_WAKE-Pad13)") (class "Default")
      (node (ref "WIFI/BT") (pin "13") (pinfunction "WL_HOST_WAKE_13") (pintype "bidirectional"))
    )
    (net (code "289") (name "{slash}RESET") (class "Default")
      (node (ref "C13") (pin "1") (pinfunction "1_1") (pintype "passive"))
      (node (ref "JTAG-MCU") (pin "P12") (pinfunction "T_NRST_P12") (pintype "bidirectional"))
      (node (ref "MCU") (pin "14") (pinfunction "NRST_14") (pintype "bidirectional"))
      (node (ref "RESET") (pin "2") (pinfunction "B_2") (pintype "bidirectional"))
    )
  )
)
